# M868Hvrs2.net
KiCad netlist of a schematic drawn in EAGLE
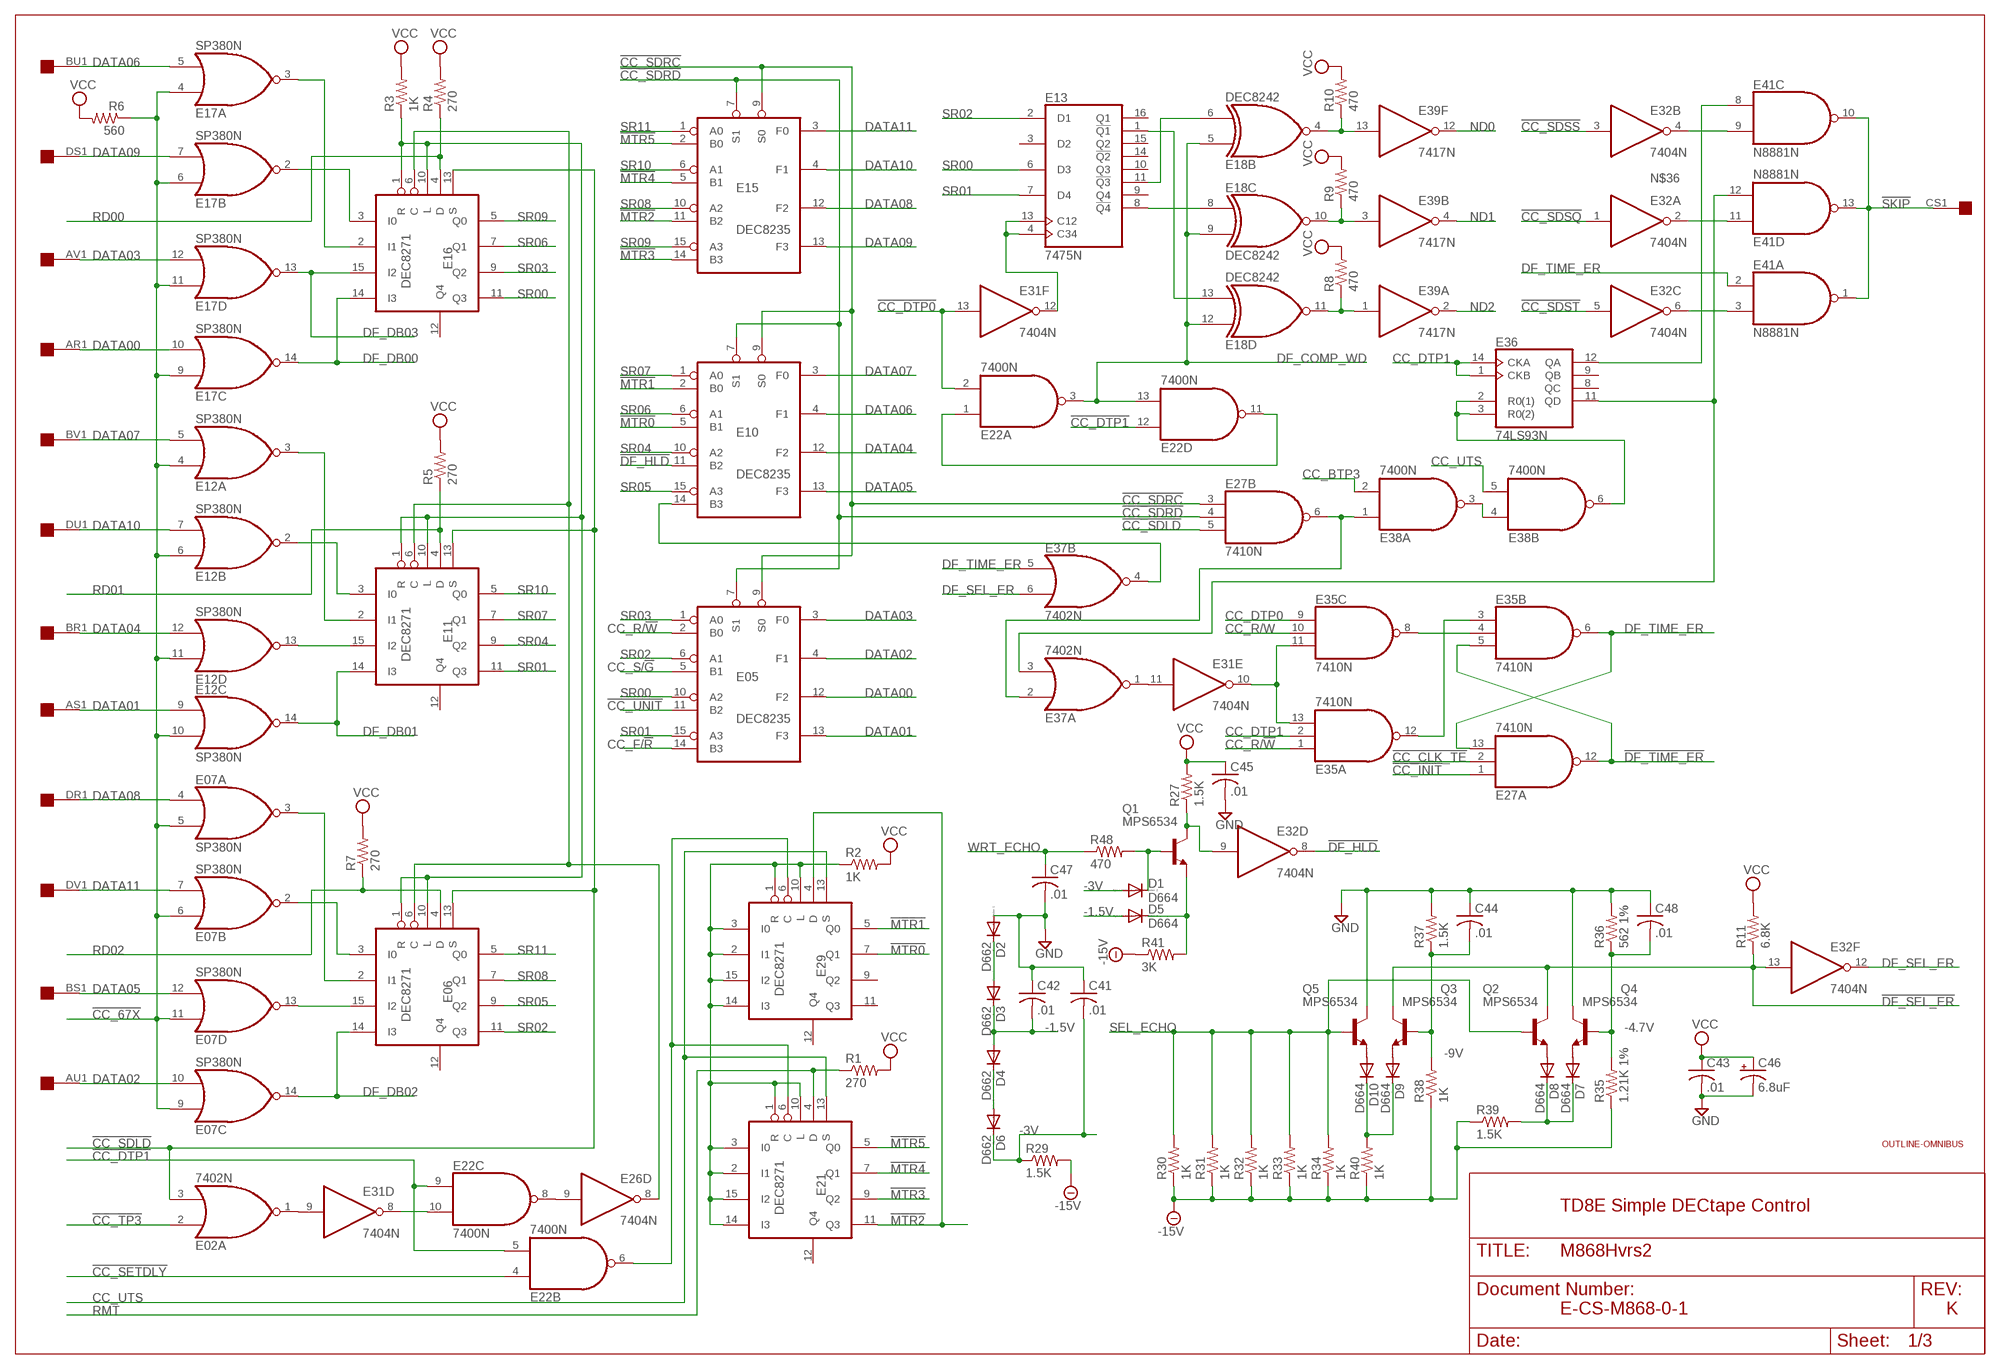
[diagram p0: schematic, sheet 1]
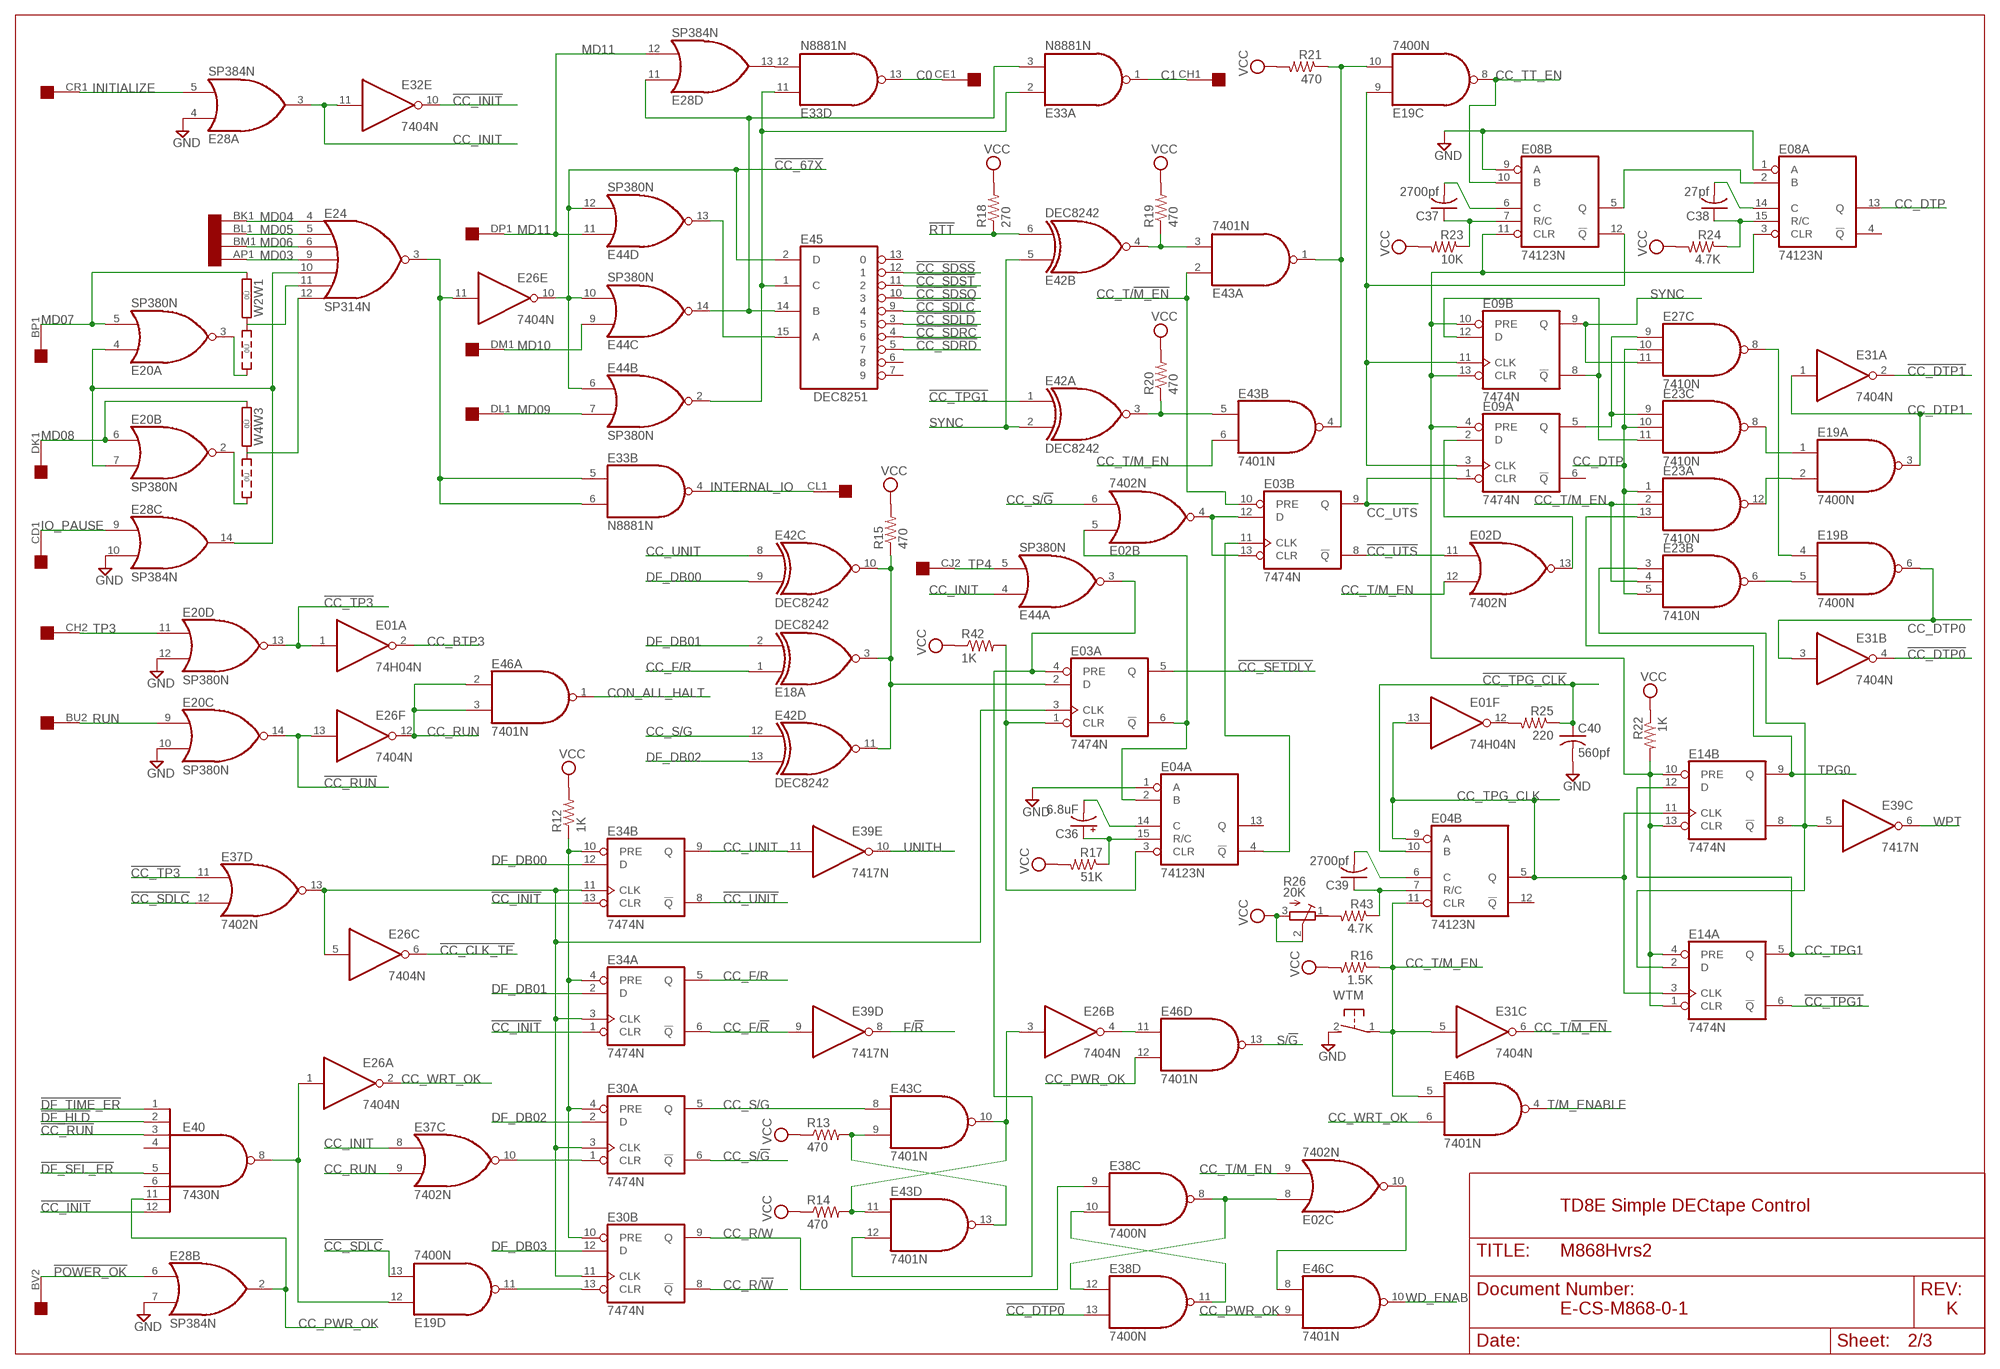
[diagram p1: schematic, sheet 2]
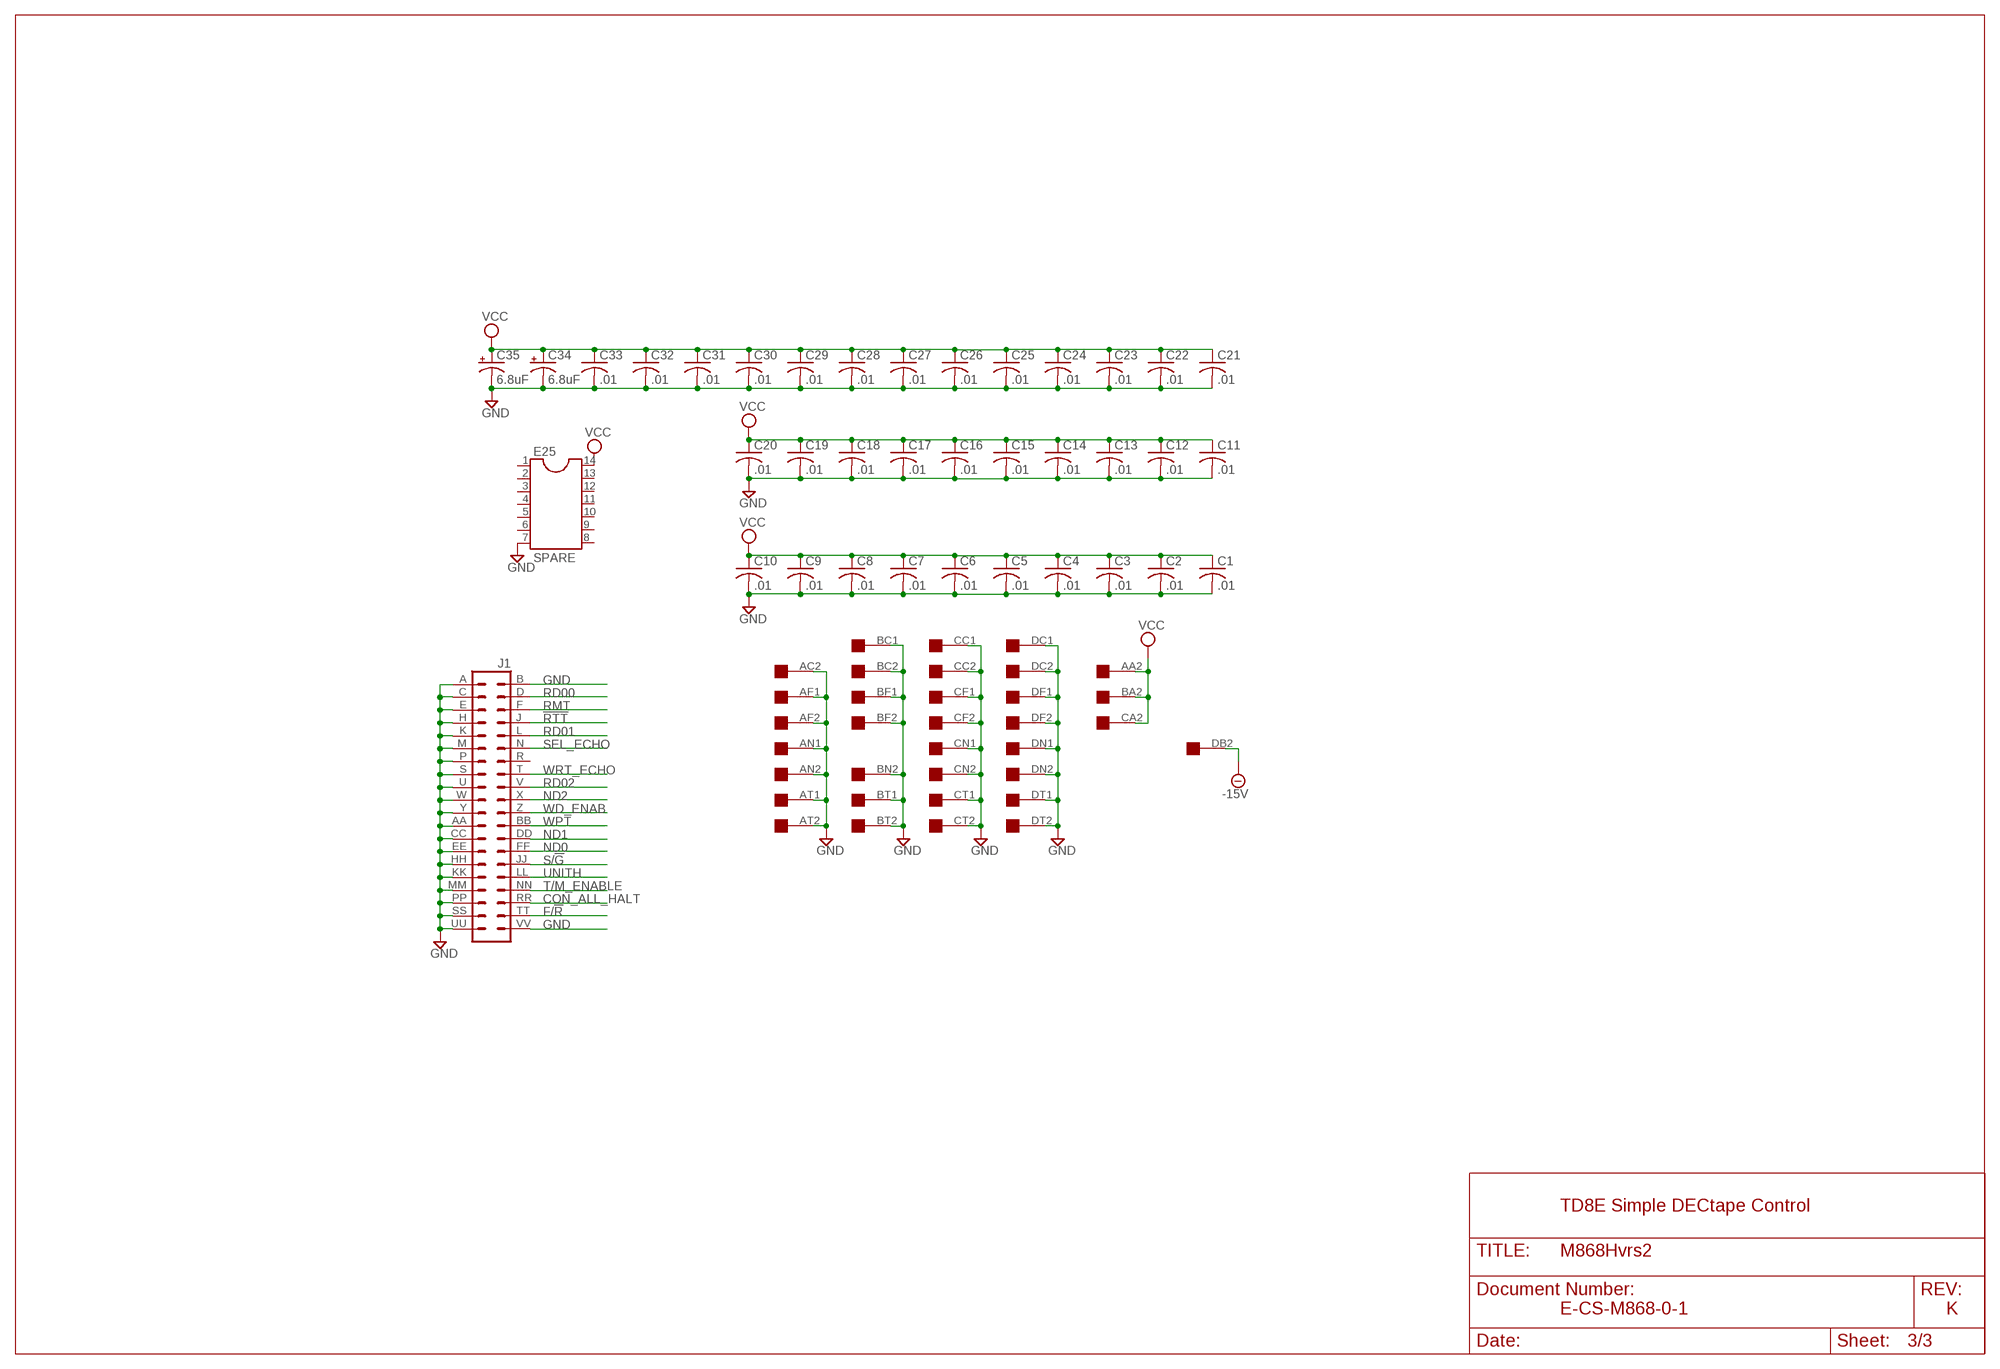
[diagram p2: schematic, sheet 3]

(export (version "E")
  (design (tool "Eeschema 10.0.6"))
  (components
    (comp (ref "C41")
      (value ".01")
      (footprint "eagle-import:C050-025X075")
      (libsource (lib "eagle-import") (part "C-US050-025X075"))
    )
    (comp (ref "C42")
      (value ".01")
      (footprint "eagle-import:C050-025X075")
      (libsource (lib "eagle-import") (part "C-US050-025X075"))
    )
    (comp (ref "C43")
      (value ".01")
      (footprint "eagle-import:C050-025X075")
      (libsource (lib "eagle-import") (part "C-US050-025X075"))
    )
    (comp (ref "C44")
      (value ".01")
      (footprint "eagle-import:C050-025X075")
      (libsource (lib "eagle-import") (part "C-US050-025X075"))
    )
    (comp (ref "C45")
      (value ".01")
      (footprint "eagle-import:C050-025X075")
      (libsource (lib "eagle-import") (part "C-US050-025X075"))
    )
    (comp (ref "C46")
      (value "6.8uF")
      (footprint "eagle-import:E12-8")
      (libsource (lib "eagle-import") (part "CPOL-USE20-8AXIAL"))
    )
    (comp (ref "C47")
      (value ".01")
      (footprint "eagle-import:C050-025X075")
      (libsource (lib "eagle-import") (part "C-US050-025X075"))
    )
    (comp (ref "C48")
      (value ".01")
      (footprint "eagle-import:C050-025X075")
      (libsource (lib "eagle-import") (part "C-US050-025X075"))
    )
    (comp (ref "D1")
      (value "D664")
      (footprint "eagle-import:DO35-10")
      (libsource (lib "eagle-import") (part "1N4148DO35-10"))
    )
    (comp (ref "D2")
      (value "D662")
      (footprint "eagle-import:DO35-10")
      (libsource (lib "eagle-import") (part "1N4148DO35-10"))
    )
    (comp (ref "D3")
      (value "D662")
      (footprint "eagle-import:DO35-10")
      (libsource (lib "eagle-import") (part "1N4148DO35-10"))
    )
    (comp (ref "D4")
      (value "D662")
      (footprint "eagle-import:DO35-10")
      (libsource (lib "eagle-import") (part "1N4148DO35-10"))
    )
    (comp (ref "D5")
      (value "D664")
      (footprint "eagle-import:DO35-10")
      (libsource (lib "eagle-import") (part "1N4148DO35-10"))
    )
    (comp (ref "D6")
      (value "D662")
      (footprint "eagle-import:DO35-10")
      (libsource (lib "eagle-import") (part "1N4148DO35-10"))
    )
    (comp (ref "D7")
      (value "D664")
      (footprint "eagle-import:DO35-10")
      (libsource (lib "eagle-import") (part "1N4148DO35-10"))
    )
    (comp (ref "D8")
      (value "D664")
      (footprint "eagle-import:DO35-10")
      (libsource (lib "eagle-import") (part "1N4148DO35-10"))
    )
    (comp (ref "D9")
      (value "D664")
      (footprint "eagle-import:DO35-10")
      (libsource (lib "eagle-import") (part "1N4148DO35-10"))
    )
    (comp (ref "D10")
      (value "D664")
      (footprint "eagle-import:DO35-10")
      (libsource (lib "eagle-import") (part "1N4148DO35-10"))
    )
    (comp (ref "E02")
      (value "7402N")
      (footprint "eagle-import:DIL14")
      (libsource (lib "eagle-import") (part "7402N"))
    )
    (comp (ref "E05")
      (value "DEC8235")
      (footprint "eagle-import:DIL16")
      (libsource (lib "eagle-import") (part "DEC8235"))
    )
    (comp (ref "E06")
      (value "DEC8271")
      (footprint "eagle-import:DIL16")
      (libsource (lib "eagle-import") (part "DEC8271"))
    )
    (comp (ref "E07")
      (value "SP380N")
      (footprint "eagle-import:DIL14")
      (libsource (lib "eagle-import") (part "SP380N"))
    )
    (comp (ref "E10")
      (value "DEC8235")
      (footprint "eagle-import:DIL16")
      (libsource (lib "eagle-import") (part "DEC8235"))
    )
    (comp (ref "E11")
      (value "DEC8271")
      (footprint "eagle-import:DIL16")
      (libsource (lib "eagle-import") (part "DEC8271"))
    )
    (comp (ref "E12")
      (value "SP380N")
      (footprint "eagle-import:DIL14")
      (libsource (lib "eagle-import") (part "SP380N"))
    )
    (comp (ref "E13")
      (value "7475N")
      (footprint "eagle-import:DIL16")
      (libsource (lib "eagle-import") (part "7475N"))
    )
    (comp (ref "E15")
      (value "DEC8235")
      (footprint "eagle-import:DIL16")
      (libsource (lib "eagle-import") (part "DEC8235"))
    )
    (comp (ref "E16")
      (value "DEC8271")
      (footprint "eagle-import:DIL16")
      (libsource (lib "eagle-import") (part "DEC8271"))
    )
    (comp (ref "E17")
      (value "SP380N")
      (footprint "eagle-import:DIL14")
      (libsource (lib "eagle-import") (part "SP380N"))
    )
    (comp (ref "E18")
      (value "DEC8242")
      (footprint "eagle-import:DIL14")
      (libsource (lib "eagle-import") (part "74266NLS"))
    )
    (comp (ref "E21")
      (value "DEC8271")
      (footprint "eagle-import:DIL16")
      (libsource (lib "eagle-import") (part "DEC8271"))
    )
    (comp (ref "E22")
      (value "7400N")
      (footprint "eagle-import:DIL14")
      (libsource (lib "eagle-import") (part "7400N"))
    )
    (comp (ref "E26")
      (value "7404N")
      (footprint "eagle-import:DIL14")
      (libsource (lib "eagle-import") (part "7404N"))
    )
    (comp (ref "E27")
      (value "7410N")
      (footprint "eagle-import:DIL14")
      (libsource (lib "eagle-import") (part "7410N"))
    )
    (comp (ref "E29")
      (value "DEC8271")
      (footprint "eagle-import:DIL16")
      (libsource (lib "eagle-import") (part "DEC8271"))
    )
    (comp (ref "E31")
      (value "7404N")
      (footprint "eagle-import:DIL14")
      (libsource (lib "eagle-import") (part "7404N"))
    )
    (comp (ref "E32")
      (value "7404N")
      (footprint "eagle-import:DIL14")
      (libsource (lib "eagle-import") (part "7404N"))
    )
    (comp (ref "E35")
      (value "7410N")
      (footprint "eagle-import:DIL14")
      (libsource (lib "eagle-import") (part "7410N"))
    )
    (comp (ref "E36")
      (value "74LS93N")
      (footprint "eagle-import:DIL14")
      (libsource (lib "eagle-import") (part "7493NLS"))
    )
    (comp (ref "E37")
      (value "7402N")
      (footprint "eagle-import:DIL14")
      (libsource (lib "eagle-import") (part "7402N"))
    )
    (comp (ref "E38")
      (value "7400N")
      (footprint "eagle-import:DIL14")
      (libsource (lib "eagle-import") (part "7400N"))
    )
    (comp (ref "E39")
      (value "7417N")
      (footprint "eagle-import:DIL14")
      (libsource (lib "eagle-import") (part "7417N"))
    )
    (comp (ref "E41")
      (value "N8881N")
      (footprint "eagle-import:DIL14")
      (libsource (lib "eagle-import") (part "N8881N"))
    )
    (comp (ref "EDGE$")
      (value "QUAD")
      (footprint "eagle-import:EDGE-CON8")
      (libsource (lib "eagle-import") (part "QUAD"))
    )
    (comp (ref "Q1")
      (value "MPS6534")
      (footprint "eagle-import:TO5")
      (libsource (lib "eagle-import") (part "2N2219"))
    )
    (comp (ref "Q2")
      (value "MPS6534")
      (footprint "eagle-import:TO5")
      (libsource (lib "eagle-import") (part "2N2219"))
    )
    (comp (ref "Q3")
      (value "MPS6534")
      (footprint "eagle-import:TO5")
      (libsource (lib "eagle-import") (part "2N2219"))
    )
    (comp (ref "Q4")
      (value "MPS6534")
      (footprint "eagle-import:TO5")
      (libsource (lib "eagle-import") (part "2N2219"))
    )
    (comp (ref "Q5")
      (value "MPS6534")
      (footprint "eagle-import:TO5")
      (libsource (lib "eagle-import") (part "2N2219"))
    )
    (comp (ref "R1")
      (value "270")
      (footprint "eagle-import:0207_10")
      (libsource (lib "eagle-import") (part "R-US_0207/10"))
    )
    (comp (ref "R2")
      (value "1K")
      (footprint "eagle-import:0207_10")
      (libsource (lib "eagle-import") (part "R-US_0207/10"))
    )
    (comp (ref "R3")
      (value "1K")
      (footprint "eagle-import:0207_10")
      (libsource (lib "eagle-import") (part "R-US_0207/10"))
    )
    (comp (ref "R4")
      (value "270")
      (footprint "eagle-import:0207_10")
      (libsource (lib "eagle-import") (part "R-US_0207/10"))
    )
    (comp (ref "R5")
      (value "270")
      (footprint "eagle-import:0207_10")
      (libsource (lib "eagle-import") (part "R-US_0207/10"))
    )
    (comp (ref "R6")
      (value "560")
      (footprint "eagle-import:0207_10")
      (libsource (lib "eagle-import") (part "R-US_0207/10"))
    )
    (comp (ref "R7")
      (value "270")
      (footprint "eagle-import:0207_10")
      (libsource (lib "eagle-import") (part "R-US_0207/10"))
    )
    (comp (ref "R8")
      (value "470")
      (footprint "eagle-import:0207_10")
      (libsource (lib "eagle-import") (part "R-US_0207/10"))
    )
    (comp (ref "R9")
      (value "470")
      (footprint "eagle-import:0207_10")
      (libsource (lib "eagle-import") (part "R-US_0207/10"))
    )
    (comp (ref "R10")
      (value "470")
      (footprint "eagle-import:0207_10")
      (libsource (lib "eagle-import") (part "R-US_0207/10"))
    )
    (comp (ref "R11")
      (value "6.8K")
      (footprint "eagle-import:0207_10")
      (libsource (lib "eagle-import") (part "R-US_0207/10"))
    )
    (comp (ref "R27")
      (value "1.5K")
      (footprint "eagle-import:0207_10")
      (libsource (lib "eagle-import") (part "R-US_0207/10"))
    )
    (comp (ref "R29")
      (value "1.5K")
      (footprint "eagle-import:0207_10")
      (libsource (lib "eagle-import") (part "R-US_0207/10"))
    )
    (comp (ref "R30")
      (value "1K")
      (footprint "eagle-import:0207_10")
      (libsource (lib "eagle-import") (part "R-US_0207/10"))
    )
    (comp (ref "R31")
      (value "1K")
      (footprint "eagle-import:0207_10")
      (libsource (lib "eagle-import") (part "R-US_0207/10"))
    )
    (comp (ref "R32")
      (value "1K")
      (footprint "eagle-import:0207_10")
      (libsource (lib "eagle-import") (part "R-US_0207/10"))
    )
    (comp (ref "R33")
      (value "1K")
      (footprint "eagle-import:0207_10")
      (libsource (lib "eagle-import") (part "R-US_0207/10"))
    )
    (comp (ref "R34")
      (value "1K")
      (footprint "eagle-import:0207_10")
      (libsource (lib "eagle-import") (part "R-US_0207/10"))
    )
    (comp (ref "R35")
      (value "1.21K 1%")
      (footprint "eagle-import:0207_15")
      (libsource (lib "eagle-import") (part "R-US_0207/15"))
    )
    (comp (ref "R36")
      (value "562 1%")
      (footprint "eagle-import:0207_15")
      (libsource (lib "eagle-import") (part "R-US_0207/15"))
    )
    (comp (ref "R37")
      (value "1.5K")
      (footprint "eagle-import:0207_10")
      (libsource (lib "eagle-import") (part "R-US_0207/10"))
    )
    (comp (ref "R38")
      (value "1K")
      (footprint "eagle-import:0207_10")
      (libsource (lib "eagle-import") (part "R-US_0207/10"))
    )
    (comp (ref "R39")
      (value "1.5K")
      (footprint "eagle-import:0207_10")
      (libsource (lib "eagle-import") (part "R-US_0207/10"))
    )
    (comp (ref "R40")
      (value "1K")
      (footprint "eagle-import:0207_10")
      (libsource (lib "eagle-import") (part "R-US_0207/10"))
    )
    (comp (ref "R41")
      (value "3K")
      (footprint "eagle-import:0207_10")
      (libsource (lib "eagle-import") (part "R-US_0207/10"))
    )
    (comp (ref "R48")
      (value "470")
      (footprint "eagle-import:0207_10")
      (libsource (lib "eagle-import") (part "R-US_0207/10"))
    )
    (comp (ref "U$1")
      (value "OUTLINE-OMNIBUS")
      (footprint "eagle-import:OMNIBUS")
      (libsource (lib "eagle-import") (part "OUTLINE-OMNIBUS"))
    )
    (comp (ref "C36")
      (value "6.8uF")
      (footprint "eagle-import:E12-8")
      (libsource (lib "eagle-import") (part "CPOL-USE20-8AXIAL"))
    )
    (comp (ref "C37")
      (value "2700pf")
      (footprint "eagle-import:C102-043X133")
      (libsource (lib "eagle-import") (part "C-US102-043X133"))
    )
    (comp (ref "C38")
      (value "27pf")
      (footprint "eagle-import:C050-025X075")
      (libsource (lib "eagle-import") (part "C-US050-025X075"))
    )
    (comp (ref "C39")
      (value "2700pf")
      (footprint "eagle-import:C102-043X133")
      (libsource (lib "eagle-import") (part "C-US102-043X133"))
    )
    (comp (ref "C40")
      (value "560pf")
      (footprint "eagle-import:C075-032X103")
      (libsource (lib "eagle-import") (part "C-US075-032X103"))
    )
    (comp (ref "E01")
      (value "74H04N")
      (footprint "eagle-import:DIL14")
      (libsource (lib "eagle-import") (part "7404NS"))
    )
    (comp (ref "E03")
      (value "7474N")
      (footprint "eagle-import:DIL14")
      (libsource (lib "eagle-import") (part "7474NS"))
    )
    (comp (ref "E04")
      (value "74123N")
      (footprint "eagle-import:DIL16")
      (libsource (lib "eagle-import") (part "74123N"))
    )
    (comp (ref "E08")
      (value "74123N")
      (footprint "eagle-import:DIL16")
      (libsource (lib "eagle-import") (part "74123N"))
    )
    (comp (ref "E09")
      (value "7474N")
      (footprint "eagle-import:DIL14")
      (libsource (lib "eagle-import") (part "7474NS"))
    )
    (comp (ref "E14")
      (value "7474N")
      (footprint "eagle-import:DIL14")
      (libsource (lib "eagle-import") (part "7474NS"))
    )
    (comp (ref "E19")
      (value "7400N")
      (footprint "eagle-import:DIL14")
      (libsource (lib "eagle-import") (part "7400N"))
    )
    (comp (ref "E20")
      (value "SP380N")
      (footprint "eagle-import:DIL14")
      (libsource (lib "eagle-import") (part "SP380N"))
    )
    (comp (ref "E23")
      (value "7410N")
      (footprint "eagle-import:DIL14")
      (libsource (lib "eagle-import") (part "7410N"))
    )
    (comp (ref "E24")
      (value "SP314N")
      (footprint "eagle-import:DIL14")
      (libsource (lib "eagle-import") (part "SP314N"))
    )
    (comp (ref "E28")
      (value "SP384N")
      (footprint "eagle-import:DIL14")
      (libsource (lib "eagle-import") (part "SP384N"))
    )
    (comp (ref "E30")
      (value "7474N")
      (footprint "eagle-import:DIL14")
      (libsource (lib "eagle-import") (part "7474NS"))
    )
    (comp (ref "E33")
      (value "N8881N")
      (footprint "eagle-import:DIL14")
      (libsource (lib "eagle-import") (part "N8881N"))
    )
    (comp (ref "E34")
      (value "7474N")
      (footprint "eagle-import:DIL14")
      (libsource (lib "eagle-import") (part "7474NS"))
    )
    (comp (ref "E40")
      (value "7430N")
      (footprint "eagle-import:DIL14")
      (libsource (lib "eagle-import") (part "7430N"))
    )
    (comp (ref "E42")
      (value "DEC8242")
      (footprint "eagle-import:DIL14")
      (libsource (lib "eagle-import") (part "74266NLS"))
    )
    (comp (ref "E43")
      (value "7401N")
      (footprint "eagle-import:DIL14")
      (libsource (lib "eagle-import") (part "7401NLS"))
    )
    (comp (ref "E44")
      (value "SP380N")
      (footprint "eagle-import:DIL14")
      (libsource (lib "eagle-import") (part "SP380N"))
    )
    (comp (ref "E45")
      (value "DEC8251")
      (footprint "eagle-import:DIL16")
      (libsource (lib "eagle-import") (part "DEC8251"))
    )
    (comp (ref "E46")
      (value "7401N")
      (footprint "eagle-import:DIL14")
      (libsource (lib "eagle-import") (part "7401NLS"))
    )
    (comp (ref "R12")
      (value "1K")
      (footprint "eagle-import:0207_10")
      (libsource (lib "eagle-import") (part "R-US_0207/10"))
    )
    (comp (ref "R13")
      (value "470")
      (footprint "eagle-import:0207_10")
      (libsource (lib "eagle-import") (part "R-US_0207/10"))
    )
    (comp (ref "R14")
      (value "470")
      (footprint "eagle-import:0207_10")
      (libsource (lib "eagle-import") (part "R-US_0207/10"))
    )
    (comp (ref "R15")
      (value "470")
      (footprint "eagle-import:0207_10")
      (libsource (lib "eagle-import") (part "R-US_0207/10"))
    )
    (comp (ref "R16")
      (value "1.5K")
      (footprint "eagle-import:0207_10")
      (libsource (lib "eagle-import") (part "R-US_0207/10"))
    )
    (comp (ref "R17")
      (value "51K")
      (footprint "eagle-import:0207_10")
      (libsource (lib "eagle-import") (part "R-US_0207/10"))
    )
    (comp (ref "R18")
      (value "270")
      (footprint "eagle-import:0207_10")
      (libsource (lib "eagle-import") (part "R-US_0207/10"))
    )
    (comp (ref "R19")
      (value "470")
      (footprint "eagle-import:0207_10")
      (libsource (lib "eagle-import") (part "R-US_0207/10"))
    )
    (comp (ref "R20")
      (value "470")
      (footprint "eagle-import:0207_10")
      (libsource (lib "eagle-import") (part "R-US_0207/10"))
    )
    (comp (ref "R21")
      (value "470")
      (footprint "eagle-import:0207_10")
      (libsource (lib "eagle-import") (part "R-US_0207/10"))
    )
    (comp (ref "R22")
      (value "1K")
      (footprint "eagle-import:0207_10")
      (libsource (lib "eagle-import") (part "R-US_0207/10"))
    )
    (comp (ref "R23")
      (value "10K")
      (footprint "eagle-import:0207_10")
      (libsource (lib "eagle-import") (part "R-US_0207/10"))
    )
    (comp (ref "R24")
      (value "4.7K")
      (footprint "eagle-import:0207_10")
      (libsource (lib "eagle-import") (part "R-US_0207/10"))
    )
    (comp (ref "R25")
      (value "220")
      (footprint "eagle-import:0207_10")
      (libsource (lib "eagle-import") (part "R-US_0207/10"))
    )
    (comp (ref "R26")
      (value "20K")
      (footprint "eagle-import:3006Y")
      (libsource (lib "eagle-import") (part "275P"))
    )
    (comp (ref "R42")
      (value "1K")
      (footprint "eagle-import:0207_10")
      (libsource (lib "eagle-import") (part "R-US_0207/10"))
    )
    (comp (ref "R43")
      (value "4.7K")
      (footprint "eagle-import:0207_10")
      (libsource (lib "eagle-import") (part "R-US_0207/10"))
    )
    (comp (ref "W2W1")
      (value "0R2")
      (footprint "eagle-import:0R2_10")
      (libsource (lib "eagle-import") (part "0R2"))
    )
    (comp (ref "W4W3")
      (value "0R2")
      (footprint "eagle-import:0R2_10")
      (libsource (lib "eagle-import") (part "0R2"))
    )
    (comp (ref "WTM")
      (value "31-XX")
      (footprint "eagle-import:B3F-31XX")
      (fields (field (name "MPN") "B3F-3100"))
      (libsource (lib "eagle-import") (part "31-XX"))
    )
    (comp (ref "C1")
      (value ".01")
      (footprint "eagle-import:C050-025X075")
      (libsource (lib "eagle-import") (part "C-US050-025X075"))
    )
    (comp (ref "C2")
      (value ".01")
      (footprint "eagle-import:C050-025X075")
      (libsource (lib "eagle-import") (part "C-US050-025X075"))
    )
    (comp (ref "C3")
      (value ".01")
      (footprint "eagle-import:C050-025X075")
      (libsource (lib "eagle-import") (part "C-US050-025X075"))
    )
    (comp (ref "C4")
      (value ".01")
      (footprint "eagle-import:C050-025X075")
      (libsource (lib "eagle-import") (part "C-US050-025X075"))
    )
    (comp (ref "C5")
      (value ".01")
      (footprint "eagle-import:C050-025X075")
      (libsource (lib "eagle-import") (part "C-US050-025X075"))
    )
    (comp (ref "C6")
      (value ".01")
      (footprint "eagle-import:C050-025X075")
      (libsource (lib "eagle-import") (part "C-US050-025X075"))
    )
    (comp (ref "C7")
      (value ".01")
      (footprint "eagle-import:C050-025X075")
      (libsource (lib "eagle-import") (part "C-US050-025X075"))
    )
    (comp (ref "C8")
      (value ".01")
      (footprint "eagle-import:C050-025X075")
      (libsource (lib "eagle-import") (part "C-US050-025X075"))
    )
    (comp (ref "C9")
      (value ".01")
      (footprint "eagle-import:C050-025X075")
      (libsource (lib "eagle-import") (part "C-US050-025X075"))
    )
    (comp (ref "C10")
      (value ".01")
      (footprint "eagle-import:C050-025X075")
      (libsource (lib "eagle-import") (part "C-US050-025X075"))
    )
    (comp (ref "C11")
      (value ".01")
      (footprint "eagle-import:C050-025X075")
      (libsource (lib "eagle-import") (part "C-US050-025X075"))
    )
    (comp (ref "C12")
      (value ".01")
      (footprint "eagle-import:C050-025X075")
      (libsource (lib "eagle-import") (part "C-US050-025X075"))
    )
    (comp (ref "C13")
      (value ".01")
      (footprint "eagle-import:C050-025X075")
      (libsource (lib "eagle-import") (part "C-US050-025X075"))
    )
    (comp (ref "C14")
      (value ".01")
      (footprint "eagle-import:C050-025X075")
      (libsource (lib "eagle-import") (part "C-US050-025X075"))
    )
    (comp (ref "C15")
      (value ".01")
      (footprint "eagle-import:C050-025X075")
      (libsource (lib "eagle-import") (part "C-US050-025X075"))
    )
    (comp (ref "C16")
      (value ".01")
      (footprint "eagle-import:C050-025X075")
      (libsource (lib "eagle-import") (part "C-US050-025X075"))
    )
    (comp (ref "C17")
      (value ".01")
      (footprint "eagle-import:C050-025X075")
      (libsource (lib "eagle-import") (part "C-US050-025X075"))
    )
    (comp (ref "C18")
      (value ".01")
      (footprint "eagle-import:C050-025X075")
      (libsource (lib "eagle-import") (part "C-US050-025X075"))
    )
    (comp (ref "C19")
      (value ".01")
      (footprint "eagle-import:C050-025X075")
      (libsource (lib "eagle-import") (part "C-US050-025X075"))
    )
    (comp (ref "C20")
      (value ".01")
      (footprint "eagle-import:C050-025X075")
      (libsource (lib "eagle-import") (part "C-US050-025X075"))
    )
    (comp (ref "C21")
      (value ".01")
      (footprint "eagle-import:C050-025X075")
      (libsource (lib "eagle-import") (part "C-US050-025X075"))
    )
    (comp (ref "C22")
      (value ".01")
      (footprint "eagle-import:C050-025X075")
      (libsource (lib "eagle-import") (part "C-US050-025X075"))
    )
    (comp (ref "C23")
      (value ".01")
      (footprint "eagle-import:C050-025X075")
      (libsource (lib "eagle-import") (part "C-US050-025X075"))
    )
    (comp (ref "C24")
      (value ".01")
      (footprint "eagle-import:C050-025X075")
      (libsource (lib "eagle-import") (part "C-US050-025X075"))
    )
    (comp (ref "C25")
      (value ".01")
      (footprint "eagle-import:C050-025X075")
      (libsource (lib "eagle-import") (part "C-US050-025X075"))
    )
    (comp (ref "C26")
      (value ".01")
      (footprint "eagle-import:C050-025X075")
      (libsource (lib "eagle-import") (part "C-US050-025X075"))
    )
    (comp (ref "C27")
      (value ".01")
      (footprint "eagle-import:C050-025X075")
      (libsource (lib "eagle-import") (part "C-US050-025X075"))
    )
    (comp (ref "C28")
      (value ".01")
      (footprint "eagle-import:C050-025X075")
      (libsource (lib "eagle-import") (part "C-US050-025X075"))
    )
    (comp (ref "C29")
      (value ".01")
      (footprint "eagle-import:C050-025X075")
      (libsource (lib "eagle-import") (part "C-US050-025X075"))
    )
    (comp (ref "C30")
      (value ".01")
      (footprint "eagle-import:C050-025X075")
      (libsource (lib "eagle-import") (part "C-US050-025X075"))
    )
    (comp (ref "C31")
      (value ".01")
      (footprint "eagle-import:C050-025X075")
      (libsource (lib "eagle-import") (part "C-US050-025X075"))
    )
    (comp (ref "C32")
      (value ".01")
      (footprint "eagle-import:C050-025X075")
      (libsource (lib "eagle-import") (part "C-US050-025X075"))
    )
    (comp (ref "C33")
      (value ".01")
      (footprint "eagle-import:C050-025X075")
      (libsource (lib "eagle-import") (part "C-US050-025X075"))
    )
    (comp (ref "C34")
      (value "6.8uF")
      (footprint "eagle-import:E12-8")
      (libsource (lib "eagle-import") (part "CPOL-USE20-8AXIAL"))
    )
    (comp (ref "C35")
      (value "6.8uF")
      (footprint "eagle-import:E12-8")
      (libsource (lib "eagle-import") (part "CPOL-USE20-8AXIAL"))
    )
    (comp (ref "E25")
      (value "SPARE")
      (footprint "eagle-import:DIL14")
      (libsource (lib "eagle-import") (part "DIL14"))
    )
    (comp (ref "J1")
      (value "DEC40PINH")
      (footprint "eagle-import:DEC40PINH")
      (libsource (lib "eagle-import") (part "DEC40PINH"))
    )
  )
  (nets
    (net (code "1") (name "-1.5V") (class "Default")
      (node (ref "C42") (pin "2") (pinfunction "2_2") (pintype "passive"))
      (node (ref "D3") (pin "C") (pinfunction "C_C") (pintype "passive"))
      (node (ref "D4") (pin "A") (pinfunction "A_A") (pintype "passive"))
      (node (ref "D5") (pin "A") (pinfunction "A_A") (pintype "passive"))
    )
    (net (code "2") (name "-3V") (class "Default")
      (node (ref "C41") (pin "2") (pinfunction "2_2") (pintype "passive"))
      (node (ref "D1") (pin "A") (pinfunction "A_A") (pintype "passive"))
      (node (ref "D6") (pin "C") (pinfunction "C_C") (pintype "passive"))
      (node (ref "R29") (pin "1") (pinfunction "1_1") (pintype "passive"))
    )
    (net (code "3") (name "-4.7V") (class "Default")
      (node (ref "C48") (pin "2") (pinfunction "2_2") (pintype "passive"))
      (node (ref "Q4") (pin "2") (pinfunction "B_2") (pintype "passive"))
      (node (ref "R35") (pin "2") (pinfunction "2_2") (pintype "passive"))
      (node (ref "R36") (pin "1") (pinfunction "1_1") (pintype "passive"))
    )
    (net (code "4") (name "-9V") (class "Default")
      (node (ref "C44") (pin "2") (pinfunction "2_2") (pintype "passive"))
      (node (ref "Q3") (pin "2") (pinfunction "B_2") (pintype "passive"))
      (node (ref "R37") (pin "1") (pinfunction "1_1") (pintype "passive"))
      (node (ref "R38") (pin "2") (pinfunction "2_2") (pintype "passive"))
    )
    (net (code "5") (name "-15V") (class "Default")
      (node (ref "EDGE$") (pin "DB2") (pinfunction "1_DB2") (pintype "bidirectional"))
      (node (ref "R29") (pin "2") (pinfunction "2_2") (pintype "passive"))
      (node (ref "R30") (pin "1") (pinfunction "1_1") (pintype "passive"))
      (node (ref "R31") (pin "1") (pinfunction "1_1") (pintype "passive"))
      (node (ref "R32") (pin "1") (pinfunction "1_1") (pintype "passive"))
      (node (ref "R33") (pin "1") (pinfunction "1_1") (pintype "passive"))
      (node (ref "R34") (pin "1") (pinfunction "1_1") (pintype "passive"))
      (node (ref "R35") (pin "1") (pinfunction "1_1") (pintype "passive"))
      (node (ref "R38") (pin "1") (pinfunction "1_1") (pintype "passive"))
      (node (ref "R39") (pin "1") (pinfunction "1_1") (pintype "passive"))
      (node (ref "R40") (pin "1") (pinfunction "1_1") (pintype "passive"))
      (node (ref "R41") (pin "1") (pinfunction "1_1") (pintype "passive"))
    )
    (net (code "6") (name "C0") (class "Default")
      (node (ref "E33") (pin "13") (pinfunction "O_13") (pintype "open_collector"))
      (node (ref "EDGE$") (pin "CE1") (pinfunction "1_CE1") (pintype "bidirectional"))
    )
    (net (code "7") (name "C1") (class "Default")
      (node (ref "E33") (pin "1") (pinfunction "O_1") (pintype "open_collector"))
      (node (ref "EDGE$") (pin "CH1") (pinfunction "1_CH1") (pintype "bidirectional"))
    )
    (net (code "8") (name "CC_BTP3") (class "Default")
      (node (ref "E01") (pin "2") (pinfunction "O_2") (pintype "output"))
      (node (ref "E38") (pin "2") (pinfunction "I1_2") (pintype "input"))
    )
    (net (code "9") (name "CC_DTP") (class "Default")
      (node (ref "E08") (pin "13") (pinfunction "Q_13") (pintype "output"))
      (node (ref "E23") (pin "1") (pinfunction "I0_1") (pintype "input"))
      (node (ref "E23") (pin "10") (pinfunction "I1_10") (pintype "input"))
      (node (ref "E23") (pin "5") (pinfunction "I2_5") (pintype "input"))
      (node (ref "E27") (pin "10") (pinfunction "I1_10") (pintype "input"))
    )
    (net (code "10") (name "CC_DTP0") (class "Default")
      (node (ref "E19") (pin "6") (pinfunction "O_6") (pintype "output"))
      (node (ref "E31") (pin "3") (pinfunction "I_3") (pintype "input"))
      (node (ref "E35") (pin "9") (pinfunction "I0_9") (pintype "input"))
    )
    (net (code "11") (name "CC_DTP1") (class "Default")
      (node (ref "E19") (pin "3") (pinfunction "O_3") (pintype "output"))
      (node (ref "E31") (pin "1") (pinfunction "I_1") (pintype "input"))
      (node (ref "E35") (pin "2") (pinfunction "I1_2") (pintype "input"))
      (node (ref "E36") (pin "1") (pinfunction "CKB_1") (pintype "input"))
      (node (ref "E36") (pin "14") (pinfunction "CKA_14") (pintype "input"))
    )
    (net (code "12") (name "CC_F{slash}R") (class "Default")
      (node (ref "E18") (pin "1") (pinfunction "I0_1") (pintype "input"))
      (node (ref "E34") (pin "5") (pinfunction "Q_5") (pintype "output"))
    )
    (net (code "13") (name "CC_F{slash}~{R}") (class "Default")
      (node (ref "E05") (pin "14") (pinfunction "B3_14") (pintype "input"))
      (node (ref "E34") (pin "6") (pinfunction "~{Q}_6") (pintype "output"))
      (node (ref "E39") (pin "9") (pinfunction "I_9") (pintype "input"))
    )
    (net (code "14") (name "CC_INIT") (class "Default")
      (node (ref "E28") (pin "3") (pinfunction "O_3") (pintype "output"))
      (node (ref "E32") (pin "11") (pinfunction "I_11") (pintype "input"))
      (node (ref "E37") (pin "8") (pinfunction "I0_8") (pintype "input"))
      (node (ref "E44") (pin "4") (pinfunction "I0_4") (pintype "input"))
    )
    (net (code "15") (name "CC_PWR_OK") (class "Default")
      (node (ref "E28") (pin "2") (pinfunction "O_2") (pintype "output"))
      (node (ref "E40") (pin "11") (pinfunction "I6_11") (pintype "input"))
      (node (ref "E46") (pin "12") (pinfunction "I1_12") (pintype "input"))
      (node (ref "E46") (pin "9") (pinfunction "I1_9") (pintype "input"))
    )
    (net (code "16") (name "CC_RUN") (class "Default")
      (node (ref "E26") (pin "12") (pinfunction "O_12") (pintype "output"))
      (node (ref "E37") (pin "9") (pinfunction "I1_9") (pintype "input"))
      (node (ref "E46") (pin "2") (pinfunction "I0_2") (pintype "input"))
      (node (ref "E46") (pin "3") (pinfunction "I1_3") (pintype "input"))
    )
    (net (code "17") (name "CC_R{slash}W") (class "Default")
      (node (ref "E30") (pin "9") (pinfunction "Q_9") (pintype "output"))
      (node (ref "E35") (pin "10") (pinfunction "I1_10") (pintype "input"))
      (node (ref "E38") (pin "9") (pinfunction "I0_9") (pintype "input"))
    )
    (net (code "18") (name "CC_R{slash}~{W}") (class "Default")
      (node (ref "E05") (pin "2") (pinfunction "B0_2") (pintype "input"))
      (node (ref "E30") (pin "8") (pinfunction "~{Q}_8") (pintype "output"))
      (node (ref "E35") (pin "1") (pinfunction "I0_1") (pintype "input"))
    )
    (net (code "19") (name "CC_S{slash}G") (class "Default")
      (node (ref "E30") (pin "5") (pinfunction "Q_5") (pintype "output"))
      (node (ref "E42") (pin "12") (pinfunction "I0_12") (pintype "input"))
      (node (ref "E43") (pin "8") (pinfunction "I0_8") (pintype "input"))
    )
    (net (code "20") (name "CC_S{slash}~{G}") (class "Default")
      (node (ref "E02") (pin "6") (pinfunction "I1_6") (pintype "input"))
      (node (ref "E05") (pin "5") (pinfunction "B1_5") (pintype "input"))
      (node (ref "E30") (pin "6") (pinfunction "~{Q}_6") (pintype "output"))
    )
    (net (code "21") (name "CC_TPG1") (class "Default")
      (node (ref "E14") (pin "12") (pinfunction "D_12") (pintype "input"))
      (node (ref "E14") (pin "5") (pinfunction "Q_5") (pintype "output"))
    )
    (net (code "22") (name "CC_TPG_CLK") (class "Default")
      (node (ref "E01") (pin "13") (pinfunction "I_13") (pintype "input"))
      (node (ref "E04") (pin "5") (pinfunction "Q_5") (pintype "output"))
      (node (ref "E04") (pin "9") (pinfunction "A_9") (pintype "input"))
      (node (ref "E14") (pin "11") (pinfunction "CLK_11") (pintype "input"))
      (node (ref "E14") (pin "3") (pinfunction "CLK_3") (pintype "input"))
    )
    (net (code "23") (name "CC_TT_EN") (class "Default")
      (node (ref "E08") (pin "10") (pinfunction "B_10") (pintype "input"))
      (node (ref "E19") (pin "8") (pinfunction "O_8") (pintype "output"))
    )
    (net (code "24") (name "CC_T{slash}M_EN") (class "Default")
      (node (ref "E02") (pin "12") (pinfunction "I1_12") (pintype "input"))
      (node (ref "E02") (pin "9") (pinfunction "I1_9") (pintype "input"))
      (node (ref "E04") (pin "11") (pinfunction "CLR_11") (pintype "input"))
      (node (ref "E23") (pin "2") (pinfunction "I1_2") (pintype "input"))
      (node (ref "E23") (pin "4") (pinfunction "I1_4") (pintype "input"))
      (node (ref "E31") (pin "5") (pinfunction "I_5") (pintype "input"))
      (node (ref "E43") (pin "6") (pinfunction "I1_6") (pintype "input"))
      (node (ref "E46") (pin "5") (pinfunction "I0_5") (pintype "input"))
      (node (ref "R16") (pin "1") (pinfunction "1_1") (pintype "passive"))
      (node (ref "WTM") (pin "1") (pinfunction "P_1") (pintype "passive"))
    )
    (net (code "25") (name "CC_T{slash}~{M_EN}") (class "Default")
      (node (ref "E03") (pin "10") (pinfunction "PRE_10") (pintype "input"))
      (node (ref "E31") (pin "6") (pinfunction "O_6") (pintype "output"))
      (node (ref "E43") (pin "2") (pinfunction "I0_2") (pintype "input"))
    )
    (net (code "26") (name "CC_UNIT") (class "Default")
      (node (ref "E34") (pin "9") (pinfunction "Q_9") (pintype "output"))
      (node (ref "E39") (pin "11") (pinfunction "I_11") (pintype "input"))
      (node (ref "E42") (pin "8") (pinfunction "I0_8") (pintype "input"))
    )
    (net (code "27") (name "CC_UTS") (class "Default")
      (node (ref "E03") (pin "9") (pinfunction "Q_9") (pintype "output"))
      (node (ref "E09") (pin "1") (pinfunction "CLR_1") (pintype "input"))
      (node (ref "E21") (pin "13") (pinfunction "S_13") (pintype "input"))
      (node (ref "E29") (pin "13") (pinfunction "S_13") (pintype "input"))
      (node (ref "E38") (pin "5") (pinfunction "I1_5") (pintype "input"))
    )
    (net (code "28") (name "CC_WRT_OK") (class "Default")
      (node (ref "E26") (pin "2") (pinfunction "O_2") (pintype "output"))
      (node (ref "E46") (pin "6") (pinfunction "I1_6") (pintype "input"))
    )
    (net (code "29") (name "CON_ALL_HALT") (class "Default")
      (node (ref "E46") (pin "1") (pinfunction "O_1") (pintype "open_collector"))
      (node (ref "J1") (pin "RR") (pinfunction "36_RR") (pintype "bidirectional"))
    )
    (net (code "30") (name "DATA00") (class "Default")
      (node (ref "E05") (pin "12") (pinfunction "F2_12") (pintype "open_collector"))
      (node (ref "E17") (pin "10") (pinfunction "I1_10") (pintype "input"))
      (node (ref "EDGE$") (pin "AR1") (pinfunction "1_AR1") (pintype "bidirectional"))
    )
    (net (code "31") (name "DATA01") (class "Default")
      (node (ref "E05") (pin "13") (pinfunction "F3_13") (pintype "open_collector"))
      (node (ref "E12") (pin "9") (pinfunction "I0_9") (pintype "input"))
      (node (ref "EDGE$") (pin "AS1") (pinfunction "1_AS1") (pintype "bidirectional"))
    )
    (net (code "32") (name "DATA02") (class "Default")
      (node (ref "E05") (pin "4") (pinfunction "F1_4") (pintype "open_collector"))
      (node (ref "E07") (pin "10") (pinfunction "I1_10") (pintype "input"))
      (node (ref "EDGE$") (pin "AU1") (pinfunction "1_AU1") (pintype "bidirectional"))
    )
    (net (code "33") (name "DATA03") (class "Default")
      (node (ref "E05") (pin "3") (pinfunction "F0_3") (pintype "open_collector"))
      (node (ref "E17") (pin "12") (pinfunction "I1_12") (pintype "input"))
      (node (ref "EDGE$") (pin "AV1") (pinfunction "1_AV1") (pintype "bidirectional"))
    )
    (net (code "34") (name "DATA04") (class "Default")
      (node (ref "E10") (pin "12") (pinfunction "F2_12") (pintype "open_collector"))
      (node (ref "E12") (pin "12") (pinfunction "I1_12") (pintype "input"))
      (node (ref "EDGE$") (pin "BR1") (pinfunction "1_BR1") (pintype "bidirectional"))
    )
    (net (code "35") (name "DATA05") (class "Default")
      (node (ref "E07") (pin "12") (pinfunction "I1_12") (pintype "input"))
      (node (ref "E10") (pin "13") (pinfunction "F3_13") (pintype "open_collector"))
      (node (ref "EDGE$") (pin "BS1") (pinfunction "1_BS1") (pintype "bidirectional"))
    )
    (net (code "36") (name "DATA06") (class "Default")
      (node (ref "E10") (pin "4") (pinfunction "F1_4") (pintype "open_collector"))
      (node (ref "E17") (pin "5") (pinfunction "I1_5") (pintype "input"))
      (node (ref "EDGE$") (pin "BU1") (pinfunction "1_BU1") (pintype "bidirectional"))
    )
    (net (code "37") (name "DATA07") (class "Default")
      (node (ref "E10") (pin "3") (pinfunction "F0_3") (pintype "open_collector"))
      (node (ref "E12") (pin "5") (pinfunction "I1_5") (pintype "input"))
      (node (ref "EDGE$") (pin "BV1") (pinfunction "1_BV1") (pintype "bidirectional"))
    )
    (net (code "38") (name "DATA08") (class "Default")
      (node (ref "E07") (pin "4") (pinfunction "I0_4") (pintype "input"))
      (node (ref "E15") (pin "12") (pinfunction "F2_12") (pintype "open_collector"))
      (node (ref "EDGE$") (pin "DR1") (pinfunction "1_DR1") (pintype "bidirectional"))
    )
    (net (code "39") (name "DATA09") (class "Default")
      (node (ref "E15") (pin "13") (pinfunction "F3_13") (pintype "open_collector"))
      (node (ref "E17") (pin "7") (pinfunction "I1_7") (pintype "input"))
      (node (ref "EDGE$") (pin "DS1") (pinfunction "1_DS1") (pintype "bidirectional"))
    )
    (net (code "40") (name "DATA10") (class "Default")
      (node (ref "E12") (pin "7") (pinfunction "I1_7") (pintype "input"))
      (node (ref "E15") (pin "4") (pinfunction "F1_4") (pintype "open_collector"))
      (node (ref "EDGE$") (pin "DU1") (pinfunction "1_DU1") (pintype "bidirectional"))
    )
    (net (code "41") (name "DATA11") (class "Default")
      (node (ref "E07") (pin "7") (pinfunction "I1_7") (pintype "input"))
      (node (ref "E15") (pin "3") (pinfunction "F0_3") (pintype "open_collector"))
      (node (ref "EDGE$") (pin "DV1") (pinfunction "1_DV1") (pintype "bidirectional"))
    )
    (net (code "42") (name "DF_COMP_WD") (class "Default")
      (node (ref "E18") (pin "12") (pinfunction "I0_12") (pintype "input"))
      (node (ref "E18") (pin "5") (pinfunction "I0_5") (pintype "input"))
      (node (ref "E18") (pin "9") (pinfunction "I1_9") (pintype "input"))
      (node (ref "E22") (pin "13") (pinfunction "I1_13") (pintype "input"))
      (node (ref "E22") (pin "3") (pinfunction "O_3") (pintype "output"))
    )
    (net (code "43") (name "DF_DB00") (class "Default")
      (node (ref "E16") (pin "14") (pinfunction "I3_14") (pintype "input"))
      (node (ref "E17") (pin "14") (pinfunction "O_14") (pintype "output"))
      (node (ref "E34") (pin "12") (pinfunction "D_12") (pintype "input"))
      (node (ref "E42") (pin "9") (pinfunction "I1_9") (pintype "input"))
    )
    (net (code "44") (name "DF_DB01") (class "Default")
      (node (ref "E11") (pin "14") (pinfunction "I3_14") (pintype "input"))
      (node (ref "E12") (pin "14") (pinfunction "O_14") (pintype "output"))
      (node (ref "E18") (pin "2") (pinfunction "I1_2") (pintype "input"))
      (node (ref "E34") (pin "2") (pinfunction "D_2") (pintype "input"))
    )
    (net (code "45") (name "DF_DB02") (class "Default")
      (node (ref "E06") (pin "14") (pinfunction "I3_14") (pintype "input"))
      (node (ref "E07") (pin "14") (pinfunction "O_14") (pintype "output"))
      (node (ref "E30") (pin "2") (pinfunction "D_2") (pintype "input"))
      (node (ref "E42") (pin "13") (pinfunction "I1_13") (pintype "input"))
    )
    (net (code "46") (name "DF_DB03") (class "Default")
      (node (ref "E16") (pin "15") (pinfunction "I2_15") (pintype "input"))
      (node (ref "E17") (pin "13") (pinfunction "O_13") (pintype "output"))
      (node (ref "E30") (pin "12") (pinfunction "D_12") (pintype "input"))
    )
    (net (code "47") (name "DF_SEL_ER") (class "Default")
      (node (ref "E32") (pin "12") (pinfunction "O_12") (pintype "output"))
      (node (ref "E37") (pin "6") (pinfunction "I1_6") (pintype "input"))
    )
    (net (code "48") (name "DF_TIME_ER") (class "Default")
      (node (ref "E27") (pin "13") (pinfunction "I2_13") (pintype "input"))
      (node (ref "E35") (pin "6") (pinfunction "O_6") (pintype "output"))
      (node (ref "E37") (pin "5") (pinfunction "I0_5") (pintype "input"))
      (node (ref "E41") (pin "2") (pinfunction "I0_2") (pintype "input"))
    )
    (net (code "49") (name "F{slash}~{R}") (class "Default")
      (node (ref "E39") (pin "8") (pinfunction "O_8") (pintype "open_collector"))
      (node (ref "J1") (pin "TT") (pinfunction "38_TT") (pintype "bidirectional"))
    )
    (net (code "50") (name "GND") (class "Default")
      (node (ref "C1") (pin "2") (pinfunction "2_2") (pintype "passive"))
      (node (ref "C10") (pin "2") (pinfunction "2_2") (pintype "passive"))
      (node (ref "C11") (pin "2") (pinfunction "2_2") (pintype "passive"))
      (node (ref "C12") (pin "2") (pinfunction "2_2") (pintype "passive"))
      (node (ref "C13") (pin "2") (pinfunction "2_2") (pintype "passive"))
      (node (ref "C14") (pin "2") (pinfunction "2_2") (pintype "passive"))
      (node (ref "C15") (pin "2") (pinfunction "2_2") (pintype "passive"))
      (node (ref "C16") (pin "2") (pinfunction "2_2") (pintype "passive"))
      (node (ref "C17") (pin "2") (pinfunction "2_2") (pintype "passive"))
      (node (ref "C18") (pin "2") (pinfunction "2_2") (pintype "passive"))
      (node (ref "C19") (pin "2") (pinfunction "2_2") (pintype "passive"))
      (node (ref "C2") (pin "2") (pinfunction "2_2") (pintype "passive"))
      (node (ref "C20") (pin "2") (pinfunction "2_2") (pintype "passive"))
      (node (ref "C21") (pin "2") (pinfunction "2_2") (pintype "passive"))
      (node (ref "C22") (pin "2") (pinfunction "2_2") (pintype "passive"))
      (node (ref "C23") (pin "2") (pinfunction "2_2") (pintype "passive"))
      (node (ref "C24") (pin "2") (pinfunction "2_2") (pintype "passive"))
      (node (ref "C25") (pin "2") (pinfunction "2_2") (pintype "passive"))
      (node (ref "C26") (pin "2") (pinfunction "2_2") (pintype "passive"))
      (node (ref "C27") (pin "2") (pinfunction "2_2") (pintype "passive"))
      (node (ref "C28") (pin "2") (pinfunction "2_2") (pintype "passive"))
      (node (ref "C29") (pin "2") (pinfunction "2_2") (pintype "passive"))
      (node (ref "C3") (pin "2") (pinfunction "2_2") (pintype "passive"))
      (node (ref "C30") (pin "2") (pinfunction "2_2") (pintype "passive"))
      (node (ref "C31") (pin "2") (pinfunction "2_2") (pintype "passive"))
      (node (ref "C32") (pin "2") (pinfunction "2_2") (pintype "passive"))
      (node (ref "C33") (pin "2") (pinfunction "2_2") (pintype "passive"))
      (node (ref "C34") (pin "-") (pinfunction "-_-") (pintype "passive"))
      (node (ref "C35") (pin "-") (pinfunction "-_-") (pintype "passive"))
      (node (ref "C4") (pin "2") (pinfunction "2_2") (pintype "passive"))
      (node (ref "C40") (pin "2") (pinfunction "2_2") (pintype "passive"))
      (node (ref "C41") (pin "1") (pinfunction "1_1") (pintype "passive"))
      (node (ref "C42") (pin "1") (pinfunction "1_1") (pintype "passive"))
      (node (ref "C43") (pin "2") (pinfunction "2_2") (pintype "passive"))
      (node (ref "C44") (pin "1") (pinfunction "1_1") (pintype "passive"))
      (node (ref "C45") (pin "2") (pinfunction "2_2") (pintype "passive"))
      (node (ref "C46") (pin "-") (pinfunction "-_-") (pintype "passive"))
      (node (ref "C47") (pin "2") (pinfunction "2_2") (pintype "passive"))
      (node (ref "C48") (pin "1") (pinfunction "1_1") (pintype "passive"))
      (node (ref "C5") (pin "2") (pinfunction "2_2") (pintype "passive"))
      (node (ref "C6") (pin "2") (pinfunction "2_2") (pintype "passive"))
      (node (ref "C7") (pin "2") (pinfunction "2_2") (pintype "passive"))
      (node (ref "C8") (pin "2") (pinfunction "2_2") (pintype "passive"))
      (node (ref "C9") (pin "2") (pinfunction "2_2") (pintype "passive"))
      (node (ref "D2") (pin "A") (pinfunction "A_A") (pintype "passive"))
      (node (ref "E04") (pin "1") (pinfunction "A_1") (pintype "input"))
      (node (ref "E08") (pin "1") (pinfunction "A_1") (pintype "input"))
      (node (ref "E08") (pin "9") (pinfunction "A_9") (pintype "input"))
      (node (ref "E20") (pin "10") (pinfunction "I1_10") (pintype "input"))
      (node (ref "E20") (pin "12") (pinfunction "I1_12") (pintype "input"))
      (node (ref "E25") (pin "7") (pinfunction "7_7") (pintype "passive"))
      (node (ref "E28") (pin "10") (pinfunction "I1_10") (pintype "input"))
      (node (ref "E28") (pin "4") (pinfunction "I0_4") (pintype "input"))
      (node (ref "E28") (pin "7") (pinfunction "I1_7") (pintype "input"))
      (node (ref "EDGE$") (pin "AC2") (pinfunction "1_AC2") (pintype "bidirectional"))
      (node (ref "EDGE$") (pin "AF1") (pinfunction "1_AF1") (pintype "bidirectional"))
      (node (ref "EDGE$") (pin "AF2") (pinfunction "1_AF2") (pintype "bidirectional"))
      (node (ref "EDGE$") (pin "AN1") (pinfunction "1_AN1") (pintype "bidirectional"))
      (node (ref "EDGE$") (pin "AN2") (pinfunction "1_AN2") (pintype "bidirectional"))
      (node (ref "EDGE$") (pin "AT1") (pinfunction "1_AT1") (pintype "bidirectional"))
      (node (ref "EDGE$") (pin "AT2") (pinfunction "1_AT2") (pintype "bidirectional"))
      (node (ref "EDGE$") (pin "BC1") (pinfunction "1_BC1") (pintype "bidirectional"))
      (node (ref "EDGE$") (pin "BC2") (pinfunction "1_BC2") (pintype "bidirectional"))
      (node (ref "EDGE$") (pin "BF1") (pinfunction "1_BF1") (pintype "bidirectional"))
      (node (ref "EDGE$") (pin "BF2") (pinfunction "1_BF2") (pintype "bidirectional"))
      (node (ref "EDGE$") (pin "BN2") (pinfunction "1_BN2") (pintype "bidirectional"))
      (node (ref "EDGE$") (pin "BT1") (pinfunction "1_BT1") (pintype "bidirectional"))
      (node (ref "EDGE$") (pin "BT2") (pinfunction "1_BT2") (pintype "bidirectional"))
      (node (ref "EDGE$") (pin "CC1") (pinfunction "1_CC1") (pintype "bidirectional"))
      (node (ref "EDGE$") (pin "CC2") (pinfunction "1_CC2") (pintype "bidirectional"))
      (node (ref "EDGE$") (pin "CF1") (pinfunction "1_CF1") (pintype "bidirectional"))
      (node (ref "EDGE$") (pin "CF2") (pinfunction "1_CF2") (pintype "bidirectional"))
      (node (ref "EDGE$") (pin "CN1") (pinfunction "1_CN1") (pintype "bidirectional"))
      (node (ref "EDGE$") (pin "CN2") (pinfunction "1_CN2") (pintype "bidirectional"))
      (node (ref "EDGE$") (pin "CT1") (pinfunction "1_CT1") (pintype "bidirectional"))
      (node (ref "EDGE$") (pin "CT2") (pinfunction "1_CT2") (pintype "bidirectional"))
      (node (ref "EDGE$") (pin "DC1") (pinfunction "1_DC1") (pintype "bidirectional"))
      (node (ref "EDGE$") (pin "DC2") (pinfunction "1_DC2") (pintype "bidirectional"))
      (node (ref "EDGE$") (pin "DF1") (pinfunction "1_DF1") (pintype "bidirectional"))
      (node (ref "EDGE$") (pin "DF2") (pinfunction "1_DF2") (pintype "bidirectional"))
      (node (ref "EDGE$") (pin "DN1") (pinfunction "1_DN1") (pintype "bidirectional"))
      (node (ref "EDGE$") (pin "DN2") (pinfunction "1_DN2") (pintype "bidirectional"))
      (node (ref "EDGE$") (pin "DT1") (pinfunction "1_DT1") (pintype "bidirectional"))
      (node (ref "EDGE$") (pin "DT2") (pinfunction "1_DT2") (pintype "bidirectional"))
      (node (ref "J1") (pin "A") (pinfunction "1_A") (pintype "bidirectional"))
      (node (ref "J1") (pin "AA") (pinfunction "23_AA") (pintype "bidirectional"))
      (node (ref "J1") (pin "B") (pinfunction "2_B") (pintype "bidirectional"))
      (node (ref "J1") (pin "C") (pinfunction "3_C") (pintype "bidirectional"))
      (node (ref "J1") (pin "CC") (pinfunction "25_CC") (pintype "bidirectional"))
      (node (ref "J1") (pin "E") (pinfunction "5_E") (pintype "bidirectional"))
      (node (ref "J1") (pin "EE") (pinfunction "27_EE") (pintype "bidirectional"))
      (node (ref "J1") (pin "H") (pinfunction "7_H") (pintype "bidirectional"))
      (node (ref "J1") (pin "HH") (pinfunction "29_HH") (pintype "bidirectional"))
      (node (ref "J1") (pin "K") (pinfunction "9_K") (pintype "bidirectional"))
      (node (ref "J1") (pin "KK") (pinfunction "31_KK") (pintype "bidirectional"))
      (node (ref "J1") (pin "M") (pinfunction "11_M") (pintype "bidirectional"))
      (node (ref "J1") (pin "MM") (pinfunction "33_MM") (pintype "bidirectional"))
      (node (ref "J1") (pin "P") (pinfunction "13_P") (pintype "bidirectional"))
      (node (ref "J1") (pin "PP") (pinfunction "35_PP") (pintype "bidirectional"))
      (node (ref "J1") (pin "S") (pinfunction "15_S") (pintype "bidirectional"))
      (node (ref "J1") (pin "SS") (pinfunction "37_SS") (pintype "bidirectional"))
      (node (ref "J1") (pin "U") (pinfunction "17_U") (pintype "bidirectional"))
      (node (ref "J1") (pin "UU") (pinfunction "39_UU") (pintype "bidirectional"))
      (node (ref "J1") (pin "VV") (pinfunction "40_VV") (pintype "bidirectional"))
      (node (ref "J1") (pin "W") (pinfunction "19_W") (pintype "bidirectional"))
      (node (ref "J1") (pin "Y") (pinfunction "21_Y") (pintype "bidirectional"))
      (node (ref "Q4") (pin "3") (pinfunction "C_3") (pintype "passive"))
      (node (ref "Q5") (pin "3") (pinfunction "C_3") (pintype "passive"))
      (node (ref "R36") (pin "2") (pinfunction "2_2") (pintype "passive"))
      (node (ref "R37") (pin "2") (pinfunction "2_2") (pintype "passive"))
      (node (ref "WTM") (pin "2") (pinfunction "S_2") (pintype "passive"))
    )
    (net (code "51") (name "INITIALIZE") (class "Default")
      (node (ref "E28") (pin "5") (pinfunction "I1_5") (pintype "input"))
      (node (ref "EDGE$") (pin "CR1") (pinfunction "1_CR1") (pintype "bidirectional"))
    )
    (net (code "52") (name "INTERNAL_IO") (class "Default")
      (node (ref "E33") (pin "4") (pinfunction "O_4") (pintype "open_collector"))
      (node (ref "EDGE$") (pin "CL1") (pinfunction "1_CL1") (pintype "bidirectional"))
    )
    (net (code "53") (name "IO_PAUSE") (class "Default")
      (node (ref "E28") (pin "9") (pinfunction "I0_9") (pintype "input"))
      (node (ref "EDGE$") (pin "CD1") (pinfunction "1_CD1") (pintype "bidirectional"))
    )
    (net (code "54") (name "MD03") (class "Default")
      (node (ref "E24") (pin "9") (pinfunction "I3_9") (pintype "input"))
      (node (ref "EDGE$") (pin "AP1") (pinfunction "1_AP1") (pintype "bidirectional"))
    )
    (net (code "55") (name "MD04") (class "Default")
      (node (ref "E24") (pin "4") (pinfunction "I0_4") (pintype "input"))
      (node (ref "EDGE$") (pin "BK1") (pinfunction "1_BK1") (pintype "bidirectional"))
    )
    (net (code "56") (name "MD05") (class "Default")
      (node (ref "E24") (pin "5") (pinfunction "I1_5") (pintype "input"))
      (node (ref "EDGE$") (pin "BL1") (pinfunction "1_BL1") (pintype "bidirectional"))
    )
    (net (code "57") (name "MD06") (class "Default")
      (node (ref "E24") (pin "6") (pinfunction "I2_6") (pintype "input"))
      (node (ref "EDGE$") (pin "BM1") (pinfunction "1_BM1") (pintype "bidirectional"))
    )
    (net (code "58") (name "MD07") (class "Default")
      (node (ref "E20") (pin "5") (pinfunction "I1_5") (pintype "input"))
      (node (ref "EDGE$") (pin "BP1") (pinfunction "1_BP1") (pintype "bidirectional"))
      (node (ref "W2W1") (pin "1") (pinfunction "1_1") (pintype "passive"))
    )
    (net (code "59") (name "MD08") (class "Default")
      (node (ref "E20") (pin "6") (pinfunction "I0_6") (pintype "input"))
      (node (ref "EDGE$") (pin "DK1") (pinfunction "1_DK1") (pintype "bidirectional"))
      (node (ref "W4W3") (pin "1") (pinfunction "1_1") (pintype "passive"))
    )
    (net (code "60") (name "MD09") (class "Default")
      (node (ref "E44") (pin "7") (pinfunction "I1_7") (pintype "input"))
      (node (ref "EDGE$") (pin "DL1") (pinfunction "1_DL1") (pintype "bidirectional"))
    )
    (net (code "61") (name "MD10") (class "Default")
      (node (ref "E44") (pin "9") (pinfunction "I0_9") (pintype "input"))
      (node (ref "EDGE$") (pin "DM1") (pinfunction "1_DM1") (pintype "bidirectional"))
    )
    (net (code "62") (name "MD11") (class "Default")
      (node (ref "E28") (pin "12") (pinfunction "I1_12") (pintype "input"))
      (node (ref "E44") (pin "11") (pinfunction "I0_11") (pintype "input"))
      (node (ref "EDGE$") (pin "DP1") (pinfunction "1_DP1") (pintype "bidirectional"))
    )
    (net (code "63") (name "N$36") (class "Default")
      (node (ref "E36") (pin "11") (pinfunction "QD_11") (pintype "output"))
      (node (ref "E37") (pin "3") (pinfunction "I1_3") (pintype "input"))
      (node (ref "E41") (pin "12") (pinfunction "I1_12") (pintype "input"))
    )
    (net (code "64") (name "ND0") (class "Default")
      (node (ref "E39") (pin "12") (pinfunction "O_12") (pintype "open_collector"))
      (node (ref "J1") (pin "FF") (pinfunction "28_FF") (pintype "bidirectional"))
    )
    (net (code "65") (name "ND1") (class "Default")
      (node (ref "E39") (pin "4") (pinfunction "O_4") (pintype "open_collector"))
      (node (ref "J1") (pin "DD") (pinfunction "26_DD") (pintype "bidirectional"))
    )
    (net (code "66") (name "ND2") (class "Default")
      (node (ref "E39") (pin "2") (pinfunction "O_2") (pintype "open_collector"))
      (node (ref "J1") (pin "X") (pinfunction "20_X") (pintype "bidirectional"))
    )
    (net (code "67") (name "Net-(D2-PadC)") (class "Default")
      (node (ref "D2") (pin "C") (pinfunction "C_C") (pintype "passive"))
      (node (ref "D3") (pin "A") (pinfunction "A_A") (pintype "passive"))
    )
    (net (code "68") (name "Net-(D4-PadC)") (class "Default")
      (node (ref "D4") (pin "C") (pinfunction "C_C") (pintype "passive"))
      (node (ref "D6") (pin "A") (pinfunction "A_A") (pintype "passive"))
    )
    (net (code "69") (name "Net-(D7-PadC)") (class "Default")
      (node (ref "D7") (pin "C") (pinfunction "C_C") (pintype "passive"))
      (node (ref "D8") (pin "C") (pinfunction "C_C") (pintype "passive"))
      (node (ref "R39") (pin "2") (pinfunction "2_2") (pintype "passive"))
    )
    (net (code "70") (name "Net-(D10-PadC)") (class "Default")
      (node (ref "D10") (pin "C") (pinfunction "C_C") (pintype "passive"))
      (node (ref "D9") (pin "C") (pinfunction "C_C") (pintype "passive"))
      (node (ref "R40") (pin "2") (pinfunction "2_2") (pintype "passive"))
    )
    (net (code "71") (name "Net-(E01F-O)") (class "Default")
      (node (ref "E01") (pin "12") (pinfunction "O_12") (pintype "output"))
      (node (ref "R25") (pin "2") (pinfunction "2_2") (pintype "passive"))
    )
    (net (code "72") (name "Net-(E02A-O)") (class "Default")
      (node (ref "E02") (pin "1") (pinfunction "O_1") (pintype "output"))
      (node (ref "E31") (pin "9") (pinfunction "I_9") (pintype "input"))
    )
    (net (code "73") (name "Net-(E02B-I0)") (class "Default")
      (node (ref "E02") (pin "5") (pinfunction "I0_5") (pintype "input"))
      (node (ref "E03") (pin "6") (pinfunction "~{Q}_6") (pintype "output"))
      (node (ref "E04") (pin "2") (pinfunction "B_2") (pintype "input"))
    )
    (net (code "74") (name "Net-(E02B-O)") (class "Default")
      (node (ref "E02") (pin "4") (pinfunction "O_4") (pintype "output"))
      (node (ref "E03") (pin "12") (pinfunction "D_12") (pintype "input"))
      (node (ref "E03") (pin "13") (pinfunction "CLR_13") (pintype "input"))
    )
    (net (code "75") (name "Net-(E02C-I0)") (class "Default")
      (node (ref "E02") (pin "8") (pinfunction "I0_8") (pintype "input"))
      (node (ref "E38") (pin "12") (pinfunction "I0_12") (pintype "input"))
      (node (ref "E38") (pin "8") (pinfunction "O_8") (pintype "output"))
    )
    (net (code "76") (name "Net-(E02C-O)") (class "Default")
      (node (ref "E02") (pin "10") (pinfunction "O_10") (pintype "output"))
      (node (ref "E46") (pin "8") (pinfunction "I0_8") (pintype "input"))
    )
    (net (code "77") (name "Net-(E02D-O)") (class "Default")
      (node (ref "E02") (pin "13") (pinfunction "O_13") (pintype "output"))
      (node (ref "E09") (pin "2") (pinfunction "D_2") (pintype "input"))
    )
    (net (code "78") (name "Net-(E03A-CLK)") (class "Default")
      (node (ref "E03") (pin "3") (pinfunction "CLK_3") (pintype "input"))
      (node (ref "E26") (pin "5") (pinfunction "I_5") (pintype "input"))
      (node (ref "E30") (pin "11") (pinfunction "CLK_11") (pintype "input"))
      (node (ref "E30") (pin "3") (pinfunction "CLK_3") (pintype "input"))
      (node (ref "E34") (pin "11") (pinfunction "CLK_11") (pintype "input"))
      (node (ref "E34") (pin "3") (pinfunction "CLK_3") (pintype "input"))
      (node (ref "E37") (pin "13") (pinfunction "O_13") (pintype "output"))
    )
    (net (code "79") (name "Net-(E03A-CLR)") (class "Default")
      (node (ref "E03") (pin "1") (pinfunction "CLR_1") (pintype "input"))
      (node (ref "E04") (pin "3") (pinfunction "CLR_3") (pintype "input"))
      (node (ref "R42") (pin "2") (pinfunction "2_2") (pintype "passive"))
    )
    (net (code "80") (name "Net-(E03A-D)") (class "Default")
      (node (ref "E03") (pin "2") (pinfunction "D_2") (pintype "input"))
      (node (ref "E18") (pin "3") (pinfunction "O_3") (pintype "open_collector"))
      (node (ref "E42") (pin "10") (pinfunction "O_10") (pintype "open_collector"))
      (node (ref "E42") (pin "11") (pinfunction "O_11") (pintype "open_collector"))
      (node (ref "R15") (pin "1") (pinfunction "1_1") (pintype "passive"))
    )
    (net (code "81") (name "Net-(E03A-PRE)") (class "Default")
      (node (ref "E03") (pin "4") (pinfunction "PRE_4") (pintype "input"))
      (node (ref "E43") (pin "12") (pinfunction "I1_12") (pintype "input"))
      (node (ref "E44") (pin "3") (pinfunction "O_3") (pintype "output"))
    )
    (net (code "82") (name "Net-(E03B-CLK)") (class "Default")
      (node (ref "E03") (pin "11") (pinfunction "CLK_11") (pintype "input"))
      (node (ref "E04") (pin "4") (pinfunction "~{Q}_4") (pintype "output"))
    )
    (net (code "83") (name "Net-(E04A-C)") (class "Default")
      (node (ref "C36") (pin "-") (pinfunction "-_-") (pintype "passive"))
      (node (ref "E04") (pin "14") (pinfunction "C_14") (pintype "input"))
    )
    (net (code "84") (name "Net-(E04A-R{slash}C)") (class "Default")
      (node (ref "C36") (pin "+") (pinfunction "+_+") (pintype "passive"))
      (node (ref "E04") (pin "15") (pinfunction "R/C_15") (pintype "input"))
      (node (ref "R17") (pin "1") (pinfunction "1_1") (pintype "passive"))
    )
    (net (code "85") (name "Net-(E04B-C)") (class "Default")
      (node (ref "C39") (pin "2") (pinfunction "2_2") (pintype "passive"))
      (node (ref "E04") (pin "6") (pinfunction "C_6") (pintype "input"))
    )
    (net (code "86") (name "Net-(E04B-R{slash}C)") (class "Default")
      (node (ref "C39") (pin "1") (pinfunction "1_1") (pintype "passive"))
      (node (ref "E04") (pin "7") (pinfunction "R/C_7") (pintype "input"))
      (node (ref "R43") (pin "1") (pinfunction "1_1") (pintype "passive"))
    )
    (net (code "87") (name "Net-(E06A-C)") (class "Default")
      (node (ref "E06") (pin "6") (pinfunction "C_6") (pintype "input"))
      (node (ref "E11") (pin "6") (pinfunction "C_6") (pintype "input"))
      (node (ref "E16") (pin "6") (pinfunction "C_6") (pintype "input"))
      (node (ref "E26") (pin "8") (pinfunction "O_8") (pintype "output"))
    )
    (net (code "88") (name "Net-(E06A-I0)") (class "Default")
      (node (ref "E06") (pin "3") (pinfunction "I0_3") (pintype "input"))
      (node (ref "E07") (pin "2") (pinfunction "O_2") (pintype "output"))
    )
    (net (code "89") (name "Net-(E06A-I1)") (class "Default")
      (node (ref "E06") (pin "2") (pinfunction "I1_2") (pintype "input"))
      (node (ref "E07") (pin "3") (pinfunction "O_3") (pintype "output"))
    )
    (net (code "90") (name "Net-(E06A-I2)") (class "Default")
      (node (ref "E06") (pin "15") (pinfunction "I2_15") (pintype "input"))
      (node (ref "E07") (pin "13") (pinfunction "O_13") (pintype "output"))
    )
    (net (code "91") (name "Net-(E06A-L)") (class "Default")
      (node (ref "E06") (pin "1") (pinfunction "R_1") (pintype "input"))
      (node (ref "E06") (pin "10") (pinfunction "L_10") (pintype "input"))
      (node (ref "E11") (pin "1") (pinfunction "R_1") (pintype "input"))
      (node (ref "E11") (pin "10") (pinfunction "L_10") (pintype "input"))
      (node (ref "E16") (pin "1") (pinfunction "R_1") (pintype "input"))
      (node (ref "E16") (pin "10") (pinfunction "L_10") (pintype "input"))
      (node (ref "R3") (pin "1") (pinfunction "1_1") (pintype "passive"))
    )
    (net (code "92") (name "Net-(E08A-B)") (class "Default")
      (node (ref "E08") (pin "2") (pinfunction "B_2") (pintype "input"))
      (node (ref "E08") (pin "5") (pinfunction "Q_5") (pintype "output"))
    )
    (net (code "93") (name "Net-(E08A-C)") (class "Default")
      (node (ref "C38") (pin "2") (pinfunction "2_2") (pintype "passive"))
      (node (ref "E08") (pin "14") (pinfunction "C_14") (pintype "input"))
    )
    (net (code "94") (name "Net-(E08A-CLR)") (class "Default")
      (node (ref "E08") (pin "11") (pinfunction "CLR_11") (pintype "input"))
      (node (ref "E08") (pin "3") (pinfunction "CLR_3") (pintype "input"))
      (node (ref "E09") (pin "10") (pinfunction "PRE_10") (pintype "input"))
      (node (ref "E09") (pin "13") (pinfunction "CLR_13") (pintype "input"))
      (node (ref "E09") (pin "4") (pinfunction "PRE_4") (pintype "input"))
      (node (ref "E14") (pin "1") (pinfunction "CLR_1") (pintype "input"))
      (node (ref "E14") (pin "10") (pinfunction "PRE_10") (pintype "input"))
      (node (ref "E14") (pin "13") (pinfunction "CLR_13") (pintype "input"))
      (node (ref "E14") (pin "4") (pinfunction "PRE_4") (pintype "input"))
      (node (ref "R22") (pin "2") (pinfunction "2_2") (pintype "passive"))
    )
    (net (code "95") (name "Net-(E08A-R{slash}C)") (class "Default")
      (node (ref "C38") (pin "1") (pinfunction "1_1") (pintype "passive"))
      (node (ref "E08") (pin "15") (pinfunction "R/C_15") (pintype "input"))
      (node (ref "R24") (pin "1") (pinfunction "1_1") (pintype "passive"))
    )
    (net (code "96") (name "Net-(E08B-C)") (class "Default")
      (node (ref "C37") (pin "2") (pinfunction "2_2") (pintype "passive"))
      (node (ref "E08") (pin "6") (pinfunction "C_6") (pintype "input"))
    )
    (net (code "97") (name "Net-(E08B-R{slash}C)") (class "Default")
      (node (ref "C37") (pin "1") (pinfunction "1_1") (pintype "passive"))
      (node (ref "E08") (pin "7") (pinfunction "R/C_7") (pintype "input"))
      (node (ref "R23") (pin "1") (pinfunction "1_1") (pintype "passive"))
    )
    (net (code "98") (name "Net-(E08B-~{Q})") (class "Default")
      (node (ref "E08") (pin "12") (pinfunction "~{Q}_12") (pintype "output"))
      (node (ref "E09") (pin "11") (pinfunction "CLK_11") (pintype "input"))
      (node (ref "E09") (pin "3") (pinfunction "CLK_3") (pintype "input"))
      (node (ref "E19") (pin "9") (pinfunction "I0_9") (pintype "input"))
    )
    (net (code "99") (name "Net-(E09A-Q)") (class "Default")
      (node (ref "E09") (pin "5") (pinfunction "Q_5") (pintype "output"))
      (node (ref "E23") (pin "9") (pinfunction "I0_9") (pintype "input"))
      (node (ref "E27") (pin "9") (pinfunction "I0_9") (pintype "input"))
    )
    (net (code "100") (name "Net-(E09B-D)") (class "Default")
      (node (ref "E09") (pin "12") (pinfunction "D_12") (pintype "input"))
      (node (ref "E09") (pin "8") (pinfunction "~{Q}_8") (pintype "output"))
      (node (ref "E23") (pin "11") (pinfunction "I2_11") (pintype "input"))
    )
    (net (code "101") (name "Net-(E10A-B3)") (class "Default")
      (node (ref "E10") (pin "14") (pinfunction "B3_14") (pintype "input"))
      (node (ref "E37") (pin "4") (pinfunction "O_4") (pintype "output"))
    )
    (net (code "102") (name "Net-(E11A-I0)") (class "Default")
      (node (ref "E11") (pin "3") (pinfunction "I0_3") (pintype "input"))
      (node (ref "E12") (pin "2") (pinfunction "O_2") (pintype "output"))
    )
    (net (code "103") (name "Net-(E11A-I1)") (class "Default")
      (node (ref "E11") (pin "2") (pinfunction "I1_2") (pintype "input"))
      (node (ref "E12") (pin "3") (pinfunction "O_3") (pintype "output"))
    )
    (net (code "104") (name "Net-(E11A-I2)") (class "Default")
      (node (ref "E11") (pin "15") (pinfunction "I2_15") (pintype "input"))
      (node (ref "E12") (pin "13") (pinfunction "O_13") (pintype "output"))
    )
    (net (code "105") (name "Net-(E13A-C12)") (class "Default")
      (node (ref "E13") (pin "13") (pinfunction "C12_13") (pintype "input"))
      (node (ref "E13") (pin "4") (pinfunction "C34_4") (pintype "input"))
      (node (ref "E31") (pin "12") (pinfunction "O_12") (pintype "output"))
    )
    (net (code "106") (name "Net-(E13A-~{Q1})") (class "Default")
      (node (ref "E13") (pin "1") (pinfunction "~{Q1}_1") (pintype "output"))
      (node (ref "E18") (pin "13") (pinfunction "I1_13") (pintype "input"))
    )
    (net (code "107") (name "Net-(E13A-~{Q3})") (class "Default")
      (node (ref "E13") (pin "11") (pinfunction "~{Q3}_11") (pintype "output"))
      (node (ref "E18") (pin "6") (pinfunction "I1_6") (pintype "input"))
    )
    (net (code "108") (name "Net-(E13A-~{Q4})") (class "Default")
      (node (ref "E13") (pin "8") (pinfunction "~{Q4}_8") (pintype "output"))
      (node (ref "E18") (pin "8") (pinfunction "I0_8") (pintype "input"))
    )
    (net (code "109") (name "Net-(E14A-D)") (class "Default")
      (node (ref "E14") (pin "2") (pinfunction "D_2") (pintype "input"))
      (node (ref "E14") (pin "8") (pinfunction "~{Q}_8") (pintype "output"))
      (node (ref "E23") (pin "3") (pinfunction "I0_3") (pintype "input"))
      (node (ref "E39") (pin "5") (pinfunction "I_5") (pintype "input"))
    )
    (net (code "110") (name "Net-(E16A-I0)") (class "Default")
      (node (ref "E16") (pin "3") (pinfunction "I0_3") (pintype "input"))
      (node (ref "E17") (pin "2") (pinfunction "O_2") (pintype "output"))
    )
    (net (code "111") (name "Net-(E16A-I1)") (class "Default")
      (node (ref "E16") (pin "2") (pinfunction "I1_2") (pintype "input"))
      (node (ref "E17") (pin "3") (pinfunction "O_3") (pintype "output"))
    )
    (net (code "112") (name "Net-(E18B-O)") (class "Default")
      (node (ref "E18") (pin "4") (pinfunction "O_4") (pintype "open_collector"))
      (node (ref "E39") (pin "13") (pinfunction "I_13") (pintype "input"))
      (node (ref "R10") (pin "1") (pinfunction "1_1") (pintype "passive"))
    )
    (net (code "113") (name "Net-(E18C-O)") (class "Default")
      (node (ref "E18") (pin "10") (pinfunction "O_10") (pintype "open_collector"))
      (node (ref "E39") (pin "3") (pinfunction "I_3") (pintype "input"))
      (node (ref "R9") (pin "1") (pinfunction "1_1") (pintype "passive"))
    )
    (net (code "114") (name "Net-(E18D-O)") (class "Default")
      (node (ref "E18") (pin "11") (pinfunction "O_11") (pintype "open_collector"))
      (node (ref "E39") (pin "1") (pinfunction "I_1") (pintype "input"))
      (node (ref "R8") (pin "1") (pinfunction "1_1") (pintype "passive"))
    )
    (net (code "115") (name "Net-(E19A-I0)") (class "Default")
      (node (ref "E19") (pin "1") (pinfunction "I0_1") (pintype "input"))
      (node (ref "E23") (pin "8") (pinfunction "O_8") (pintype "output"))
    )
    (net (code "116") (name "Net-(E19A-I1)") (class "Default")
      (node (ref "E19") (pin "2") (pinfunction "I1_2") (pintype "input"))
      (node (ref "E23") (pin "12") (pinfunction "O_12") (pintype "output"))
    )
    (net (code "117") (name "Net-(E19B-I0)") (class "Default")
      (node (ref "E19") (pin "4") (pinfunction "I0_4") (pintype "input"))
      (node (ref "E27") (pin "8") (pinfunction "O_8") (pintype "output"))
    )
    (net (code "118") (name "Net-(E19B-I1)") (class "Default")
      (node (ref "E19") (pin "5") (pinfunction "I1_5") (pintype "input"))
      (node (ref "E23") (pin "6") (pinfunction "O_6") (pintype "output"))
    )
    (net (code "119") (name "Net-(E19C-I1)") (class "Default")
      (node (ref "E19") (pin "10") (pinfunction "I1_10") (pintype "input"))
      (node (ref "E43") (pin "1") (pinfunction "O_1") (pintype "open_collector"))
      (node (ref "E43") (pin "4") (pinfunction "O_4") (pintype "open_collector"))
      (node (ref "R21") (pin "1") (pinfunction "1_1") (pintype "passive"))
    )
    (net (code "120") (name "Net-(E19D-I0)") (class "Default")
      (node (ref "E19") (pin "12") (pinfunction "I0_12") (pintype "input"))
      (node (ref "E26") (pin "1") (pinfunction "I_1") (pintype "input"))
      (node (ref "E40") (pin "8") (pinfunction "O_8") (pintype "output"))
    )
    (net (code "121") (name "Net-(E19D-O)") (class "Default")
      (node (ref "E19") (pin "11") (pinfunction "O_11") (pintype "output"))
      (node (ref "E30") (pin "13") (pinfunction "CLR_13") (pintype "input"))
    )
    (net (code "122") (name "Net-(E20A-I0)") (class "Default")
      (node (ref "E20") (pin "4") (pinfunction "I0_4") (pintype "input"))
      (node (ref "E20") (pin "7") (pinfunction "I1_7") (pintype "input"))
      (node (ref "E24") (pin "10") (pinfunction "I4_10") (pintype "input"))
      (node (ref "E28") (pin "14") (pinfunction "O_14") (pintype "output"))
    )
    (net (code "123") (name "Net-(E20A-O)") (class "Default")
      (node (ref "E20") (pin "3") (pinfunction "O_3") (pintype "output"))
      (node (ref "W2W1") (pin "3") (pinfunction "3_3") (pintype "passive"))
    )
    (net (code "124") (name "Net-(E20B-O)") (class "Default")
      (node (ref "E20") (pin "2") (pinfunction "O_2") (pintype "output"))
      (node (ref "W4W3") (pin "3") (pinfunction "3_3") (pintype "passive"))
    )
    (net (code "125") (name "Net-(E21A-C)") (class "Default")
      (node (ref "E21") (pin "6") (pinfunction "C_6") (pintype "input"))
      (node (ref "E22") (pin "6") (pinfunction "O_6") (pintype "output"))
      (node (ref "E29") (pin "6") (pinfunction "C_6") (pintype "input"))
    )
    (net (code "126") (name "Net-(E21A-I0)") (class "Default")
      (node (ref "E21") (pin "1") (pinfunction "R_1") (pintype "input"))
      (node (ref "E21") (pin "10") (pinfunction "L_10") (pintype "input"))
      (node (ref "E21") (pin "14") (pinfunction "I3_14") (pintype "input"))
      (node (ref "E21") (pin "15") (pinfunction "I2_15") (pintype "input"))
      (node (ref "E21") (pin "2") (pinfunction "I1_2") (pintype "input"))
      (node (ref "E21") (pin "3") (pinfunction "I0_3") (pintype "input"))
      (node (ref "E29") (pin "1") (pinfunction "R_1") (pintype "input"))
      (node (ref "E29") (pin "10") (pinfunction "L_10") (pintype "input"))
      (node (ref "E29") (pin "14") (pinfunction "I3_14") (pintype "input"))
      (node (ref "E29") (pin "15") (pinfunction "I2_15") (pintype "input"))
      (node (ref "E29") (pin "2") (pinfunction "I1_2") (pintype "input"))
      (node (ref "E29") (pin "3") (pinfunction "I0_3") (pintype "input"))
      (node (ref "R2") (pin "1") (pinfunction "1_1") (pintype "passive"))
    )
    (net (code "127") (name "Net-(E22A-I0)") (class "Default")
      (node (ref "E22") (pin "1") (pinfunction "I0_1") (pintype "input"))
      (node (ref "E22") (pin "11") (pinfunction "O_11") (pintype "output"))
    )
    (net (code "128") (name "Net-(E22C-I1)") (class "Default")
      (node (ref "E22") (pin "10") (pinfunction "I1_10") (pintype "input"))
      (node (ref "E31") (pin "8") (pinfunction "O_8") (pintype "output"))
    )
    (net (code "129") (name "Net-(E22C-O)") (class "Default")
      (node (ref "E22") (pin "8") (pinfunction "O_8") (pintype "output"))
      (node (ref "E26") (pin "9") (pinfunction "I_9") (pintype "input"))
    )
    (net (code "130") (name "Net-(E24A-I5)") (class "Default")
      (node (ref "E24") (pin "11") (pinfunction "I5_11") (pintype "input"))
      (node (ref "W2W1") (pin "2") (pinfunction "2_2") (pintype "passive"))
    )
    (net (code "131") (name "Net-(E24A-I6)") (class "Default")
      (node (ref "E24") (pin "12") (pinfunction "I6_12") (pintype "input"))
      (node (ref "W4W3") (pin "2") (pinfunction "2_2") (pintype "passive"))
    )
    (net (code "132") (name "Net-(E24A-O)") (class "Default")
      (node (ref "E24") (pin "3") (pinfunction "O_3") (pintype "output"))
      (node (ref "E26") (pin "11") (pinfunction "I_11") (pintype "input"))
      (node (ref "E33") (pin "5") (pinfunction "I0_5") (pintype "input"))
      (node (ref "E33") (pin "6") (pinfunction "I1_6") (pintype "input"))
    )
    (net (code "133") (name "Net-(E26B-I)") (class "Default")
      (node (ref "E26") (pin "3") (pinfunction "I_3") (pintype "input"))
      (node (ref "E43") (pin "10") (pinfunction "O_10") (pintype "open_collector"))
      (node (ref "E43") (pin "11") (pinfunction "I0_11") (pintype "input"))
      (node (ref "R14") (pin "2") (pinfunction "2_2") (pintype "passive"))
    )
    (net (code "134") (name "Net-(E26B-O)") (class "Default")
      (node (ref "E26") (pin "4") (pinfunction "O_4") (pintype "output"))
      (node (ref "E46") (pin "11") (pinfunction "I0_11") (pintype "input"))
    )
    (net (code "135") (name "Net-(E27B-O)") (class "Default")
      (node (ref "E27") (pin "6") (pinfunction "O_6") (pintype "output"))
      (node (ref "E37") (pin "2") (pinfunction "I0_2") (pintype "input"))
      (node (ref "E38") (pin "1") (pinfunction "I0_1") (pintype "input"))
    )
    (net (code "136") (name "Net-(E28D-I0)") (class "Default")
      (node (ref "E28") (pin "11") (pinfunction "I0_11") (pintype "input"))
      (node (ref "E33") (pin "3") (pinfunction "I1_3") (pintype "input"))
      (node (ref "E44") (pin "14") (pinfunction "O_14") (pintype "output"))
      (node (ref "E45") (pin "14") (pinfunction "B_14") (pintype "input"))
    )
    (net (code "137") (name "Net-(E28D-O)") (class "Default")
      (node (ref "E28") (pin "13") (pinfunction "O_13") (pintype "output"))
      (node (ref "E33") (pin "12") (pinfunction "I1_12") (pintype "input"))
    )
    (net (code "138") (name "Net-(E30A-CLR)") (class "Default")
      (node (ref "E30") (pin "1") (pinfunction "CLR_1") (pintype "input"))
      (node (ref "E37") (pin "10") (pinfunction "O_10") (pintype "output"))
    )
    (net (code "139") (name "Net-(E30A-PRE)") (class "Default")
      (node (ref "E30") (pin "10") (pinfunction "PRE_10") (pintype "input"))
      (node (ref "E30") (pin "4") (pinfunction "PRE_4") (pintype "input"))
      (node (ref "E34") (pin "10") (pinfunction "PRE_10") (pintype "input"))
      (node (ref "E34") (pin "4") (pinfunction "PRE_4") (pintype "input"))
      (node (ref "R12") (pin "1") (pinfunction "1_1") (pintype "passive"))
    )
    (net (code "140") (name "Net-(E31E-I)") (class "Default")
      (node (ref "E31") (pin "11") (pinfunction "I_11") (pintype "input"))
      (node (ref "E37") (pin "1") (pinfunction "O_1") (pintype "output"))
    )
    (net (code "141") (name "Net-(E31E-O)") (class "Default")
      (node (ref "E31") (pin "10") (pinfunction "O_10") (pintype "output"))
      (node (ref "E35") (pin "11") (pinfunction "I2_11") (pintype "input"))
      (node (ref "E35") (pin "13") (pinfunction "I2_13") (pintype "input"))
    )
    (net (code "142") (name "Net-(E32A-O)") (class "Default")
      (node (ref "E32") (pin "2") (pinfunction "O_2") (pintype "output"))
      (node (ref "E41") (pin "11") (pinfunction "I0_11") (pintype "input"))
    )
    (net (code "143") (name "Net-(E32B-O)") (class "Default")
      (node (ref "E32") (pin "4") (pinfunction "O_4") (pintype "output"))
      (node (ref "E41") (pin "9") (pinfunction "I1_9") (pintype "input"))
    )
    (net (code "144") (name "Net-(E32C-O)") (class "Default")
      (node (ref "E32") (pin "6") (pinfunction "O_6") (pintype "output"))
      (node (ref "E41") (pin "3") (pinfunction "I1_3") (pintype "input"))
    )
    (net (code "145") (name "Net-(E32D-I)") (class "Default")
      (node (ref "E32") (pin "9") (pinfunction "I_9") (pintype "input"))
      (node (ref "Q1") (pin "3") (pinfunction "C_3") (pintype "passive"))
      (node (ref "R27") (pin "1") (pinfunction "1_1") (pintype "passive"))
    )
    (net (code "146") (name "Net-(E33A-I0)") (class "Default")
      (node (ref "E33") (pin "11") (pinfunction "I0_11") (pintype "input"))
      (node (ref "E33") (pin "2") (pinfunction "I0_2") (pintype "input"))
      (node (ref "E44") (pin "2") (pinfunction "O_2") (pintype "output"))
      (node (ref "E45") (pin "1") (pinfunction "C_1") (pintype "input"))
    )
    (net (code "147") (name "Net-(E35A-O)") (class "Default")
      (node (ref "E35") (pin "12") (pinfunction "O_12") (pintype "output"))
      (node (ref "E35") (pin "3") (pinfunction "I0_3") (pintype "input"))
    )
    (net (code "148") (name "Net-(E35B-I1)") (class "Default")
      (node (ref "E35") (pin "4") (pinfunction "I1_4") (pintype "input"))
      (node (ref "E35") (pin "8") (pinfunction "O_8") (pintype "output"))
    )
    (net (code "149") (name "Net-(E36A-QA)") (class "Default")
      (node (ref "E36") (pin "12") (pinfunction "QA_12") (pintype "output"))
      (node (ref "E41") (pin "8") (pinfunction "I0_8") (pintype "input"))
    )
    (net (code "150") (name "Net-(E36A-R0(1))") (class "Default")
      (node (ref "E36") (pin "2") (pinfunction "R0(1)_2") (pintype "input"))
      (node (ref "E36") (pin "3") (pinfunction "R0(2)_3") (pintype "input"))
      (node (ref "E38") (pin "6") (pinfunction "O_6") (pintype "output"))
    )
    (net (code "151") (name "Net-(E38A-O)") (class "Default")
      (node (ref "E38") (pin "3") (pinfunction "O_3") (pintype "output"))
      (node (ref "E38") (pin "4") (pinfunction "I0_4") (pintype "input"))
    )
    (net (code "152") (name "Net-(E38C-I1)") (class "Default")
      (node (ref "E38") (pin "10") (pinfunction "I1_10") (pintype "input"))
      (node (ref "E38") (pin "11") (pinfunction "O_11") (pintype "output"))
    )
    (net (code "153") (name "Net-(E42A-O)") (class "Default")
      (node (ref "E42") (pin "3") (pinfunction "O_3") (pintype "open_collector"))
      (node (ref "E43") (pin "5") (pinfunction "I0_5") (pintype "input"))
      (node (ref "R20") (pin "1") (pinfunction "1_1") (pintype "passive"))
    )
    (net (code "154") (name "Net-(E42B-O)") (class "Default")
      (node (ref "E42") (pin "4") (pinfunction "O_4") (pintype "open_collector"))
      (node (ref "E43") (pin "3") (pinfunction "I1_3") (pintype "input"))
      (node (ref "R19") (pin "1") (pinfunction "1_1") (pintype "passive"))
    )
    (net (code "155") (name "Net-(E43C-I1)") (class "Default")
      (node (ref "E43") (pin "13") (pinfunction "O_13") (pintype "open_collector"))
      (node (ref "E43") (pin "9") (pinfunction "I1_9") (pintype "input"))
      (node (ref "R13") (pin "2") (pinfunction "2_2") (pintype "passive"))
    )
    (net (code "156") (name "Net-(E44D-O)") (class "Default")
      (node (ref "E44") (pin "13") (pinfunction "O_13") (pintype "output"))
      (node (ref "E45") (pin "15") (pinfunction "A_15") (pintype "input"))
    )
    (net (code "157") (name "Net-(Q1-B)") (class "Default")
      (node (ref "D1") (pin "C") (pinfunction "C_C") (pintype "passive"))
      (node (ref "Q1") (pin "2") (pinfunction "B_2") (pintype "passive"))
      (node (ref "R48") (pin "2") (pinfunction "2_2") (pintype "passive"))
    )
    (net (code "158") (name "Net-(Q1-E)") (class "Default")
      (node (ref "D5") (pin "C") (pinfunction "C_C") (pintype "passive"))
      (node (ref "Q1") (pin "1") (pinfunction "E_1") (pintype "passive"))
      (node (ref "R41") (pin "2") (pinfunction "2_2") (pintype "passive"))
    )
    (net (code "159") (name "Net-(Q2-E)") (class "Default")
      (node (ref "D8") (pin "A") (pinfunction "A_A") (pintype "passive"))
      (node (ref "Q2") (pin "1") (pinfunction "E_1") (pintype "passive"))
    )
    (net (code "160") (name "Net-(Q3-E)") (class "Default")
      (node (ref "D9") (pin "A") (pinfunction "A_A") (pintype "passive"))
      (node (ref "Q3") (pin "1") (pinfunction "E_1") (pintype "passive"))
    )
    (net (code "161") (name "Net-(Q4-E)") (class "Default")
      (node (ref "D7") (pin "A") (pinfunction "A_A") (pintype "passive"))
      (node (ref "Q4") (pin "1") (pinfunction "E_1") (pintype "passive"))
    )
    (net (code "162") (name "Net-(Q5-E)") (class "Default")
      (node (ref "D10") (pin "A") (pinfunction "A_A") (pintype "passive"))
      (node (ref "Q5") (pin "1") (pinfunction "E_1") (pintype "passive"))
    )
    (net (code "163") (name "Net-(R26-A)") (class "Default")
      (node (ref "R26") (pin "1") (pinfunction "A_1") (pintype "passive"))
      (node (ref "R43") (pin "2") (pinfunction "2_2") (pintype "passive"))
    )
    (net (code "164") (name "RD00") (class "Default")
      (node (ref "E16") (pin "4") (pinfunction "D_4") (pintype "input"))
      (node (ref "J1") (pin "D") (pinfunction "4_D") (pintype "bidirectional"))
      (node (ref "R4") (pin "1") (pinfunction "1_1") (pintype "passive"))
    )
    (net (code "165") (name "RD01") (class "Default")
      (node (ref "E11") (pin "4") (pinfunction "D_4") (pintype "input"))
      (node (ref "J1") (pin "L") (pinfunction "10_L") (pintype "bidirectional"))
      (node (ref "R5") (pin "1") (pinfunction "1_1") (pintype "passive"))
    )
    (net (code "166") (name "RD02") (class "Default")
      (node (ref "E06") (pin "4") (pinfunction "D_4") (pintype "input"))
      (node (ref "J1") (pin "V") (pinfunction "18_V") (pintype "bidirectional"))
      (node (ref "R7") (pin "1") (pinfunction "1_1") (pintype "passive"))
    )
    (net (code "167") (name "RMT") (class "Default")
      (node (ref "E21") (pin "4") (pinfunction "D_4") (pintype "input"))
      (node (ref "J1") (pin "F") (pinfunction "6_F") (pintype "bidirectional"))
      (node (ref "R1") (pin "1") (pinfunction "1_1") (pintype "passive"))
    )
    (net (code "168") (name "RUN") (class "Default")
      (node (ref "E20") (pin "9") (pinfunction "I0_9") (pintype "input"))
      (node (ref "EDGE$") (pin "BU2") (pinfunction "1_BU2") (pintype "bidirectional"))
    )
    (net (code "169") (name "SEL_ECHO") (class "Default")
      (node (ref "J1") (pin "N") (pinfunction "12_N") (pintype "bidirectional"))
      (node (ref "Q2") (pin "2") (pinfunction "B_2") (pintype "passive"))
      (node (ref "Q5") (pin "2") (pinfunction "B_2") (pintype "passive"))
      (node (ref "R30") (pin "2") (pinfunction "2_2") (pintype "passive"))
      (node (ref "R31") (pin "2") (pinfunction "2_2") (pintype "passive"))
      (node (ref "R32") (pin "2") (pinfunction "2_2") (pintype "passive"))
      (node (ref "R33") (pin "2") (pinfunction "2_2") (pintype "passive"))
      (node (ref "R34") (pin "2") (pinfunction "2_2") (pintype "passive"))
    )
    (net (code "170") (name "SR00") (class "Default")
      (node (ref "E05") (pin "10") (pinfunction "A2_10") (pintype "input"))
      (node (ref "E13") (pin "6") (pinfunction "D3_6") (pintype "input"))
      (node (ref "E16") (pin "11") (pinfunction "Q3_11") (pintype "output"))
    )
    (net (code "171") (name "SR01") (class "Default")
      (node (ref "E05") (pin "15") (pinfunction "A3_15") (pintype "input"))
      (node (ref "E11") (pin "11") (pinfunction "Q3_11") (pintype "output"))
      (node (ref "E13") (pin "7") (pinfunction "D4_7") (pintype "input"))
    )
    (net (code "172") (name "SR02") (class "Default")
      (node (ref "E05") (pin "6") (pinfunction "A1_6") (pintype "input"))
      (node (ref "E06") (pin "11") (pinfunction "Q3_11") (pintype "output"))
      (node (ref "E13") (pin "2") (pinfunction "D1_2") (pintype "input"))
    )
    (net (code "173") (name "SR03") (class "Default")
      (node (ref "E05") (pin "1") (pinfunction "A0_1") (pintype "input"))
      (node (ref "E16") (pin "9") (pinfunction "Q2_9") (pintype "output"))
    )
    (net (code "174") (name "SR04") (class "Default")
      (node (ref "E10") (pin "10") (pinfunction "A2_10") (pintype "input"))
      (node (ref "E11") (pin "9") (pinfunction "Q2_9") (pintype "output"))
    )
    (net (code "175") (name "SR05") (class "Default")
      (node (ref "E06") (pin "9") (pinfunction "Q2_9") (pintype "output"))
      (node (ref "E10") (pin "15") (pinfunction "A3_15") (pintype "input"))
    )
    (net (code "176") (name "SR06") (class "Default")
      (node (ref "E10") (pin "6") (pinfunction "A1_6") (pintype "input"))
      (node (ref "E16") (pin "7") (pinfunction "Q1_7") (pintype "output"))
    )
    (net (code "177") (name "SR07") (class "Default")
      (node (ref "E10") (pin "1") (pinfunction "A0_1") (pintype "input"))
      (node (ref "E11") (pin "7") (pinfunction "Q1_7") (pintype "output"))
    )
    (net (code "178") (name "SR08") (class "Default")
      (node (ref "E06") (pin "7") (pinfunction "Q1_7") (pintype "output"))
      (node (ref "E15") (pin "10") (pinfunction "A2_10") (pintype "input"))
    )
    (net (code "179") (name "SR09") (class "Default")
      (node (ref "E15") (pin "15") (pinfunction "A3_15") (pintype "input"))
      (node (ref "E16") (pin "5") (pinfunction "Q0_5") (pintype "output"))
    )
    (net (code "180") (name "SR10") (class "Default")
      (node (ref "E11") (pin "5") (pinfunction "Q0_5") (pintype "output"))
      (node (ref "E15") (pin "6") (pinfunction "A1_6") (pintype "input"))
    )
    (net (code "181") (name "SR11") (class "Default")
      (node (ref "E06") (pin "5") (pinfunction "Q0_5") (pintype "output"))
      (node (ref "E15") (pin "1") (pinfunction "A0_1") (pintype "input"))
    )
    (net (code "182") (name "SYNC") (class "Default")
      (node (ref "E09") (pin "9") (pinfunction "Q_9") (pintype "output"))
      (node (ref "E27") (pin "11") (pinfunction "I2_11") (pintype "input"))
      (node (ref "E42") (pin "2") (pinfunction "I1_2") (pintype "input"))
      (node (ref "E42") (pin "5") (pinfunction "I0_5") (pintype "input"))
    )
    (net (code "183") (name "S{slash}~{G}") (class "Default")
      (node (ref "E46") (pin "13") (pinfunction "O_13") (pintype "open_collector"))
      (node (ref "J1") (pin "JJ") (pinfunction "30_JJ") (pintype "bidirectional"))
    )
    (net (code "184") (name "TP3") (class "Default")
      (node (ref "E20") (pin "11") (pinfunction "I0_11") (pintype "input"))
      (node (ref "EDGE$") (pin "CH2") (pinfunction "1_CH2") (pintype "bidirectional"))
    )
    (net (code "185") (name "TP4") (class "Default")
      (node (ref "E44") (pin "5") (pinfunction "I1_5") (pintype "input"))
      (node (ref "EDGE$") (pin "CJ2") (pinfunction "1_CJ2") (pintype "bidirectional"))
    )
    (net (code "186") (name "TPG0") (class "Default")
      (node (ref "E14") (pin "9") (pinfunction "Q_9") (pintype "output"))
      (node (ref "E23") (pin "13") (pinfunction "I2_13") (pintype "input"))
    )
    (net (code "187") (name "T{slash}M_ENABLE") (class "Default")
      (node (ref "E46") (pin "4") (pinfunction "O_4") (pintype "open_collector"))
      (node (ref "J1") (pin "NN") (pinfunction "34_NN") (pintype "bidirectional"))
    )
    (net (code "188") (name "UNITH") (class "Default")
      (node (ref "E39") (pin "10") (pinfunction "O_10") (pintype "open_collector"))
      (node (ref "J1") (pin "LL") (pinfunction "32_LL") (pintype "bidirectional"))
    )
    (net (code "189") (name "VCC") (class "Default")
      (node (ref "C1") (pin "1") (pinfunction "1_1") (pintype "passive"))
      (node (ref "C10") (pin "1") (pinfunction "1_1") (pintype "passive"))
      (node (ref "C11") (pin "1") (pinfunction "1_1") (pintype "passive"))
      (node (ref "C12") (pin "1") (pinfunction "1_1") (pintype "passive"))
      (node (ref "C13") (pin "1") (pinfunction "1_1") (pintype "passive"))
      (node (ref "C14") (pin "1") (pinfunction "1_1") (pintype "passive"))
      (node (ref "C15") (pin "1") (pinfunction "1_1") (pintype "passive"))
      (node (ref "C16") (pin "1") (pinfunction "1_1") (pintype "passive"))
      (node (ref "C17") (pin "1") (pinfunction "1_1") (pintype "passive"))
      (node (ref "C18") (pin "1") (pinfunction "1_1") (pintype "passive"))
      (node (ref "C19") (pin "1") (pinfunction "1_1") (pintype "passive"))
      (node (ref "C2") (pin "1") (pinfunction "1_1") (pintype "passive"))
      (node (ref "C20") (pin "1") (pinfunction "1_1") (pintype "passive"))
      (node (ref "C21") (pin "1") (pinfunction "1_1") (pintype "passive"))
      (node (ref "C22") (pin "1") (pinfunction "1_1") (pintype "passive"))
      (node (ref "C23") (pin "1") (pinfunction "1_1") (pintype "passive"))
      (node (ref "C24") (pin "1") (pinfunction "1_1") (pintype "passive"))
      (node (ref "C25") (pin "1") (pinfunction "1_1") (pintype "passive"))
      (node (ref "C26") (pin "1") (pinfunction "1_1") (pintype "passive"))
      (node (ref "C27") (pin "1") (pinfunction "1_1") (pintype "passive"))
      (node (ref "C28") (pin "1") (pinfunction "1_1") (pintype "passive"))
      (node (ref "C29") (pin "1") (pinfunction "1_1") (pintype "passive"))
      (node (ref "C3") (pin "1") (pinfunction "1_1") (pintype "passive"))
      (node (ref "C30") (pin "1") (pinfunction "1_1") (pintype "passive"))
      (node (ref "C31") (pin "1") (pinfunction "1_1") (pintype "passive"))
      (node (ref "C32") (pin "1") (pinfunction "1_1") (pintype "passive"))
      (node (ref "C33") (pin "1") (pinfunction "1_1") (pintype "passive"))
      (node (ref "C34") (pin "+") (pinfunction "+_+") (pintype "passive"))
      (node (ref "C35") (pin "+") (pinfunction "+_+") (pintype "passive"))
      (node (ref "C4") (pin "1") (pinfunction "1_1") (pintype "passive"))
      (node (ref "C43") (pin "1") (pinfunction "1_1") (pintype "passive"))
      (node (ref "C45") (pin "1") (pinfunction "1_1") (pintype "passive"))
      (node (ref "C46") (pin "+") (pinfunction "+_+") (pintype "passive"))
      (node (ref "C5") (pin "1") (pinfunction "1_1") (pintype "passive"))
      (node (ref "C6") (pin "1") (pinfunction "1_1") (pintype "passive"))
      (node (ref "C7") (pin "1") (pinfunction "1_1") (pintype "passive"))
      (node (ref "C8") (pin "1") (pinfunction "1_1") (pintype "passive"))
      (node (ref "C9") (pin "1") (pinfunction "1_1") (pintype "passive"))
      (node (ref "E25") (pin "14") (pinfunction "14_14") (pintype "passive"))
      (node (ref "EDGE$") (pin "AA2") (pinfunction "1_AA2") (pintype "bidirectional"))
      (node (ref "EDGE$") (pin "BA2") (pinfunction "1_BA2") (pintype "bidirectional"))
      (node (ref "EDGE$") (pin "CA2") (pinfunction "1_CA2") (pintype "bidirectional"))
      (node (ref "R1") (pin "2") (pinfunction "2_2") (pintype "passive"))
      (node (ref "R10") (pin "2") (pinfunction "2_2") (pintype "passive"))
      (node (ref "R11") (pin "2") (pinfunction "2_2") (pintype "passive"))
      (node (ref "R12") (pin "2") (pinfunction "2_2") (pintype "passive"))
      (node (ref "R13") (pin "1") (pinfunction "1_1") (pintype "passive"))
      (node (ref "R14") (pin "1") (pinfunction "1_1") (pintype "passive"))
      (node (ref "R15") (pin "2") (pinfunction "2_2") (pintype "passive"))
      (node (ref "R16") (pin "2") (pinfunction "2_2") (pintype "passive"))
      (node (ref "R17") (pin "2") (pinfunction "2_2") (pintype "passive"))
      (node (ref "R18") (pin "2") (pinfunction "2_2") (pintype "passive"))
      (node (ref "R19") (pin "2") (pinfunction "2_2") (pintype "passive"))
      (node (ref "R2") (pin "2") (pinfunction "2_2") (pintype "passive"))
      (node (ref "R20") (pin "2") (pinfunction "2_2") (pintype "passive"))
      (node (ref "R21") (pin "2") (pinfunction "2_2") (pintype "passive"))
      (node (ref "R22") (pin "1") (pinfunction "1_1") (pintype "passive"))
      (node (ref "R23") (pin "2") (pinfunction "2_2") (pintype "passive"))
      (node (ref "R24") (pin "2") (pinfunction "2_2") (pintype "passive"))
      (node (ref "R26") (pin "2") (pinfunction "S_2") (pintype "passive"))
      (node (ref "R26") (pin "3") (pinfunction "E_3") (pintype "passive"))
      (node (ref "R27") (pin "2") (pinfunction "2_2") (pintype "passive"))
      (node (ref "R3") (pin "2") (pinfunction "2_2") (pintype "passive"))
      (node (ref "R4") (pin "2") (pinfunction "2_2") (pintype "passive"))
      (node (ref "R42") (pin "1") (pinfunction "1_1") (pintype "passive"))
      (node (ref "R5") (pin "2") (pinfunction "2_2") (pintype "passive"))
      (node (ref "R6") (pin "2") (pinfunction "2_2") (pintype "passive"))
      (node (ref "R7") (pin "2") (pinfunction "2_2") (pintype "passive"))
      (node (ref "R8") (pin "2") (pinfunction "2_2") (pintype "passive"))
      (node (ref "R9") (pin "2") (pinfunction "2_2") (pintype "passive"))
    )
    (net (code "190") (name "WD_ENAB") (class "Default")
      (node (ref "E46") (pin "10") (pinfunction "O_10") (pintype "open_collector"))
      (node (ref "J1") (pin "Z") (pinfunction "22_Z") (pintype "bidirectional"))
    )
    (net (code "191") (name "WPT") (class "Default")
      (node (ref "E39") (pin "6") (pinfunction "O_6") (pintype "open_collector"))
      (node (ref "J1") (pin "BB") (pinfunction "24_BB") (pintype "bidirectional"))
    )
    (net (code "192") (name "WRT_ECHO") (class "Default")
      (node (ref "C47") (pin "1") (pinfunction "1_1") (pintype "passive"))
      (node (ref "J1") (pin "T") (pinfunction "16_T") (pintype "bidirectional"))
      (node (ref "R48") (pin "1") (pinfunction "1_1") (pintype "passive"))
    )
    (net (code "193") (name "unconnected-(E04A-Q-Pad13)") (class "Default")
      (node (ref "E04") (pin "13") (pinfunction "Q_13") (pintype "output"))
    )
    (net (code "194") (name "unconnected-(E04B-~{Q}-Pad12)") (class "Default")
      (node (ref "E04") (pin "12") (pinfunction "~{Q}_12") (pintype "output"))
    )
    (net (code "195") (name "unconnected-(E06A-Q4-Pad12)") (class "Default")
      (node (ref "E06") (pin "12") (pinfunction "Q4_12") (pintype "output"))
    )
    (net (code "196") (name "unconnected-(E08A-~{Q}-Pad4)") (class "Default")
      (node (ref "E08") (pin "4") (pinfunction "~{Q}_4") (pintype "output"))
    )
    (net (code "197") (name "unconnected-(E09A-~{Q}-Pad6)") (class "Default")
      (node (ref "E09") (pin "6") (pinfunction "~{Q}_6") (pintype "output"))
    )
    (net (code "198") (name "unconnected-(E11A-Q4-Pad12)") (class "Default")
      (node (ref "E11") (pin "12") (pinfunction "Q4_12") (pintype "output"))
    )
    (net (code "199") (name "unconnected-(E13A-D2-Pad3)") (class "Default")
      (node (ref "E13") (pin "3") (pinfunction "D2_3") (pintype "input"))
    )
    (net (code "200") (name "unconnected-(E13A-Q1-Pad16)") (class "Default")
      (node (ref "E13") (pin "16") (pinfunction "Q1_16") (pintype "output"))
    )
    (net (code "201") (name "unconnected-(E13A-Q2-Pad15)") (class "Default")
      (node (ref "E13") (pin "15") (pinfunction "Q2_15") (pintype "output"))
    )
    (net (code "202") (name "unconnected-(E13A-Q3-Pad10)") (class "Default")
      (node (ref "E13") (pin "10") (pinfunction "Q3_10") (pintype "output"))
    )
    (net (code "203") (name "unconnected-(E13A-Q4-Pad9)") (class "Default")
      (node (ref "E13") (pin "9") (pinfunction "Q4_9") (pintype "output"))
    )
    (net (code "204") (name "unconnected-(E13A-~{Q2}-Pad14)") (class "Default")
      (node (ref "E13") (pin "14") (pinfunction "~{Q2}_14") (pintype "output"))
    )
    (net (code "205") (name "unconnected-(E16A-Q4-Pad12)") (class "Default")
      (node (ref "E16") (pin "12") (pinfunction "Q4_12") (pintype "output"))
    )
    (net (code "206") (name "unconnected-(E21A-Q4-Pad12)") (class "Default")
      (node (ref "E21") (pin "12") (pinfunction "Q4_12") (pintype "output"))
    )
    (net (code "207") (name "unconnected-(E25-Pad1)") (class "Default")
      (node (ref "E25") (pin "1") (pinfunction "1_1") (pintype "passive"))
    )
    (net (code "208") (name "unconnected-(E25-Pad2)") (class "Default")
      (node (ref "E25") (pin "2") (pinfunction "2_2") (pintype "passive"))
    )
    (net (code "209") (name "unconnected-(E25-Pad3)") (class "Default")
      (node (ref "E25") (pin "3") (pinfunction "3_3") (pintype "passive"))
    )
    (net (code "210") (name "unconnected-(E25-Pad4)") (class "Default")
      (node (ref "E25") (pin "4") (pinfunction "4_4") (pintype "passive"))
    )
    (net (code "211") (name "unconnected-(E25-Pad5)") (class "Default")
      (node (ref "E25") (pin "5") (pinfunction "5_5") (pintype "passive"))
    )
    (net (code "212") (name "unconnected-(E25-Pad6)") (class "Default")
      (node (ref "E25") (pin "6") (pinfunction "6_6") (pintype "passive"))
    )
    (net (code "213") (name "unconnected-(E25-Pad8)") (class "Default")
      (node (ref "E25") (pin "8") (pinfunction "8_8") (pintype "passive"))
    )
    (net (code "214") (name "unconnected-(E25-Pad9)") (class "Default")
      (node (ref "E25") (pin "9") (pinfunction "9_9") (pintype "passive"))
    )
    (net (code "215") (name "unconnected-(E25-Pad10)") (class "Default")
      (node (ref "E25") (pin "10") (pinfunction "10_10") (pintype "passive"))
    )
    (net (code "216") (name "unconnected-(E25-Pad11)") (class "Default")
      (node (ref "E25") (pin "11") (pinfunction "11_11") (pintype "passive"))
    )
    (net (code "217") (name "unconnected-(E25-Pad12)") (class "Default")
      (node (ref "E25") (pin "12") (pinfunction "12_12") (pintype "passive"))
    )
    (net (code "218") (name "unconnected-(E25-Pad13)") (class "Default")
      (node (ref "E25") (pin "13") (pinfunction "13_13") (pintype "passive"))
    )
    (net (code "219") (name "unconnected-(E29A-Q2-Pad9)") (class "Default")
      (node (ref "E29") (pin "9") (pinfunction "Q2_9") (pintype "output"))
    )
    (net (code "220") (name "unconnected-(E29A-Q3-Pad11)") (class "Default")
      (node (ref "E29") (pin "11") (pinfunction "Q3_11") (pintype "output"))
    )
    (net (code "221") (name "unconnected-(E29A-Q4-Pad12)") (class "Default")
      (node (ref "E29") (pin "12") (pinfunction "Q4_12") (pintype "output"))
    )
    (net (code "222") (name "unconnected-(E36A-QB-Pad9)") (class "Default")
      (node (ref "E36") (pin "9") (pinfunction "QB_9") (pintype "output"))
    )
    (net (code "223") (name "unconnected-(E36A-QC-Pad8)") (class "Default")
      (node (ref "E36") (pin "8") (pinfunction "QC_8") (pintype "output"))
    )
    (net (code "224") (name "unconnected-(E40A-I3-Pad4)") (class "Default")
      (node (ref "E40") (pin "4") (pinfunction "I3_4") (pintype "input"))
    )
    (net (code "225") (name "unconnected-(E40A-I5-Pad6)") (class "Default")
      (node (ref "E40") (pin "6") (pinfunction "I5_6") (pintype "input"))
    )
    (net (code "226") (name "unconnected-(E45A-0-Pad13)") (class "Default")
      (node (ref "E45") (pin "13") (pinfunction "0_13") (pintype "output"))
    )
    (net (code "227") (name "unconnected-(E45A-8-Pad6)") (class "Default")
      (node (ref "E45") (pin "6") (pinfunction "8_6") (pintype "output"))
    )
    (net (code "228") (name "unconnected-(E45A-9-Pad7)") (class "Default")
      (node (ref "E45") (pin "7") (pinfunction "9_7") (pintype "output"))
    )
    (net (code "229") (name "unconnected-(J1-14-PadR)") (class "Default")
      (node (ref "J1") (pin "R") (pinfunction "14_R") (pintype "bidirectional"))
    )
    (net (code "230") (name "~{CC_67X}") (class "Default")
      (node (ref "E07") (pin "11") (pinfunction "I0_11") (pintype "input"))
      (node (ref "E07") (pin "5") (pinfunction "I1_5") (pintype "input"))
      (node (ref "E07") (pin "6") (pinfunction "I0_6") (pintype "input"))
      (node (ref "E07") (pin "9") (pinfunction "I0_9") (pintype "input"))
      (node (ref "E12") (pin "10") (pinfunction "I1_10") (pintype "input"))
      (node (ref "E12") (pin "11") (pinfunction "I0_11") (pintype "input"))
      (node (ref "E12") (pin "4") (pinfunction "I0_4") (pintype "input"))
      (node (ref "E12") (pin "6") (pinfunction "I0_6") (pintype "input"))
      (node (ref "E17") (pin "11") (pinfunction "I0_11") (pintype "input"))
      (node (ref "E17") (pin "4") (pinfunction "I0_4") (pintype "input"))
      (node (ref "E17") (pin "6") (pinfunction "I0_6") (pintype "input"))
      (node (ref "E17") (pin "9") (pinfunction "I0_9") (pintype "input"))
      (node (ref "E26") (pin "10") (pinfunction "O_10") (pintype "output"))
      (node (ref "E44") (pin "10") (pinfunction "I1_10") (pintype "input"))
      (node (ref "E44") (pin "12") (pinfunction "I1_12") (pintype "input"))
      (node (ref "E44") (pin "6") (pinfunction "I0_6") (pintype "input"))
      (node (ref "E45") (pin "2") (pinfunction "D_2") (pintype "input"))
      (node (ref "R6") (pin "1") (pinfunction "1_1") (pintype "passive"))
    )
    (net (code "231") (name "~{CC_CLK_TE}") (class "Default")
      (node (ref "E26") (pin "6") (pinfunction "O_6") (pintype "output"))
      (node (ref "E27") (pin "2") (pinfunction "I1_2") (pintype "input"))
    )
    (net (code "232") (name "~{CC_DTP0}") (class "Default")
      (node (ref "E22") (pin "2") (pinfunction "I1_2") (pintype "input"))
      (node (ref "E31") (pin "13") (pinfunction "I_13") (pintype "input"))
      (node (ref "E31") (pin "4") (pinfunction "O_4") (pintype "output"))
      (node (ref "E38") (pin "13") (pinfunction "I1_13") (pintype "input"))
    )
    (net (code "233") (name "~{CC_DTP1}") (class "Default")
      (node (ref "E22") (pin "12") (pinfunction "I0_12") (pintype "input"))
      (node (ref "E22") (pin "5") (pinfunction "I1_5") (pintype "input"))
      (node (ref "E22") (pin "9") (pinfunction "I0_9") (pintype "input"))
      (node (ref "E31") (pin "2") (pinfunction "O_2") (pintype "output"))
    )
    (net (code "234") (name "~{CC_INIT}") (class "Default")
      (node (ref "E27") (pin "1") (pinfunction "I0_1") (pintype "input"))
      (node (ref "E32") (pin "10") (pinfunction "O_10") (pintype "output"))
      (node (ref "E34") (pin "1") (pinfunction "CLR_1") (pintype "input"))
      (node (ref "E34") (pin "13") (pinfunction "CLR_13") (pintype "input"))
      (node (ref "E40") (pin "12") (pinfunction "I7_12") (pintype "input"))
    )
    (net (code "235") (name "~{CC_RUN}") (class "Default")
      (node (ref "E20") (pin "14") (pinfunction "O_14") (pintype "output"))
      (node (ref "E26") (pin "13") (pinfunction "I_13") (pintype "input"))
      (node (ref "E40") (pin "3") (pinfunction "I2_3") (pintype "input"))
    )
    (net (code "236") (name "~{CC_SDLC}") (class "Default")
      (node (ref "E19") (pin "13") (pinfunction "I1_13") (pintype "input"))
      (node (ref "E37") (pin "12") (pinfunction "I1_12") (pintype "input"))
      (node (ref "E45") (pin "9") (pinfunction "4_9") (pintype "output"))
    )
    (net (code "237") (name "~{CC_SDLD}") (class "Default")
      (node (ref "E02") (pin "3") (pinfunction "I1_3") (pintype "input"))
      (node (ref "E06") (pin "13") (pinfunction "S_13") (pintype "input"))
      (node (ref "E11") (pin "13") (pinfunction "S_13") (pintype "input"))
      (node (ref "E16") (pin "13") (pinfunction "S_13") (pintype "input"))
      (node (ref "E27") (pin "5") (pinfunction "I2_5") (pintype "input"))
      (node (ref "E45") (pin "3") (pinfunction "5_3") (pintype "output"))
    )
    (net (code "238") (name "~{CC_SDRC}") (class "Default")
      (node (ref "E05") (pin "9") (pinfunction "S0_9") (pintype "input"))
      (node (ref "E10") (pin "9") (pinfunction "S0_9") (pintype "input"))
      (node (ref "E15") (pin "9") (pinfunction "S0_9") (pintype "input"))
      (node (ref "E27") (pin "3") (pinfunction "I0_3") (pintype "input"))
      (node (ref "E45") (pin "4") (pinfunction "6_4") (pintype "output"))
    )
    (net (code "239") (name "~{CC_SDRD}") (class "Default")
      (node (ref "E05") (pin "7") (pinfunction "S1_7") (pintype "input"))
      (node (ref "E10") (pin "7") (pinfunction "S1_7") (pintype "input"))
      (node (ref "E15") (pin "7") (pinfunction "S1_7") (pintype "input"))
      (node (ref "E27") (pin "4") (pinfunction "I1_4") (pintype "input"))
      (node (ref "E45") (pin "5") (pinfunction "7_5") (pintype "output"))
    )
    (net (code "240") (name "~{CC_SDSQ}") (class "Default")
      (node (ref "E32") (pin "1") (pinfunction "I_1") (pintype "input"))
      (node (ref "E45") (pin "10") (pinfunction "3_10") (pintype "output"))
    )
    (net (code "241") (name "~{CC_SDSS}") (class "Default")
      (node (ref "E32") (pin "3") (pinfunction "I_3") (pintype "input"))
      (node (ref "E45") (pin "12") (pinfunction "1_12") (pintype "output"))
    )
    (net (code "242") (name "~{CC_SDST}") (class "Default")
      (node (ref "E32") (pin "5") (pinfunction "I_5") (pintype "input"))
      (node (ref "E45") (pin "11") (pinfunction "2_11") (pintype "output"))
    )
    (net (code "243") (name "~{CC_SETDLY}") (class "Default")
      (node (ref "E03") (pin "5") (pinfunction "Q_5") (pintype "output"))
      (node (ref "E22") (pin "4") (pinfunction "I0_4") (pintype "input"))
    )
    (net (code "244") (name "~{CC_TP3}") (class "Default")
      (node (ref "E01") (pin "1") (pinfunction "I_1") (pintype "input"))
      (node (ref "E02") (pin "2") (pinfunction "I0_2") (pintype "input"))
      (node (ref "E20") (pin "13") (pinfunction "O_13") (pintype "output"))
      (node (ref "E37") (pin "11") (pinfunction "I0_11") (pintype "input"))
    )
    (net (code "245") (name "~{CC_TPG1}") (class "Default")
      (node (ref "E14") (pin "6") (pinfunction "~{Q}_6") (pintype "output"))
      (node (ref "E42") (pin "1") (pinfunction "I0_1") (pintype "input"))
    )
    (net (code "246") (name "~{CC_TPG_CLK}") (class "Default")
      (node (ref "C40") (pin "1") (pinfunction "1_1") (pintype "passive"))
      (node (ref "E04") (pin "10") (pinfunction "B_10") (pintype "input"))
      (node (ref "R25") (pin "1") (pinfunction "1_1") (pintype "passive"))
    )
    (net (code "247") (name "~{CC_UNIT}") (class "Default")
      (node (ref "E05") (pin "11") (pinfunction "B2_11") (pintype "input"))
      (node (ref "E34") (pin "8") (pinfunction "~{Q}_8") (pintype "output"))
    )
    (net (code "248") (name "~{CC_UTS}") (class "Default")
      (node (ref "E02") (pin "11") (pinfunction "I0_11") (pintype "input"))
      (node (ref "E03") (pin "8") (pinfunction "~{Q}_8") (pintype "output"))
    )
    (net (code "249") (name "~{DF_HLD}") (class "Default")
      (node (ref "E10") (pin "11") (pinfunction "B2_11") (pintype "input"))
      (node (ref "E32") (pin "8") (pinfunction "O_8") (pintype "output"))
      (node (ref "E40") (pin "2") (pinfunction "I1_2") (pintype "input"))
    )
    (net (code "250") (name "~{DF_SEL_ER}") (class "Default")
      (node (ref "E32") (pin "13") (pinfunction "I_13") (pintype "input"))
      (node (ref "E40") (pin "5") (pinfunction "I4_5") (pintype "input"))
      (node (ref "Q2") (pin "3") (pinfunction "C_3") (pintype "passive"))
      (node (ref "Q3") (pin "3") (pinfunction "C_3") (pintype "passive"))
      (node (ref "R11") (pin "1") (pinfunction "1_1") (pintype "passive"))
    )
    (net (code "251") (name "~{DF_TIME_ER}") (class "Default")
      (node (ref "E27") (pin "12") (pinfunction "O_12") (pintype "output"))
      (node (ref "E35") (pin "5") (pinfunction "I2_5") (pintype "input"))
      (node (ref "E40") (pin "1") (pinfunction "I0_1") (pintype "input"))
    )
    (net (code "252") (name "~{MTR0}") (class "Default")
      (node (ref "E10") (pin "5") (pinfunction "B1_5") (pintype "input"))
      (node (ref "E29") (pin "7") (pinfunction "Q1_7") (pintype "output"))
    )
    (net (code "253") (name "~{MTR1}") (class "Default")
      (node (ref "E10") (pin "2") (pinfunction "B0_2") (pintype "input"))
      (node (ref "E29") (pin "5") (pinfunction "Q0_5") (pintype "output"))
    )
    (net (code "254") (name "~{MTR2}") (class "Default")
      (node (ref "E15") (pin "11") (pinfunction "B2_11") (pintype "input"))
      (node (ref "E21") (pin "11") (pinfunction "Q3_11") (pintype "output"))
      (node (ref "E29") (pin "4") (pinfunction "D_4") (pintype "input"))
    )
    (net (code "255") (name "~{MTR3}") (class "Default")
      (node (ref "E15") (pin "14") (pinfunction "B3_14") (pintype "input"))
      (node (ref "E21") (pin "9") (pinfunction "Q2_9") (pintype "output"))
    )
    (net (code "256") (name "~{MTR4}") (class "Default")
      (node (ref "E15") (pin "5") (pinfunction "B1_5") (pintype "input"))
      (node (ref "E21") (pin "7") (pinfunction "Q1_7") (pintype "output"))
    )
    (net (code "257") (name "~{MTR5}") (class "Default")
      (node (ref "E15") (pin "2") (pinfunction "B0_2") (pintype "input"))
      (node (ref "E21") (pin "5") (pinfunction "Q0_5") (pintype "output"))
    )
    (net (code "258") (name "~{POWER_OK}") (class "Default")
      (node (ref "E28") (pin "6") (pinfunction "I0_6") (pintype "input"))
      (node (ref "EDGE$") (pin "BV2") (pinfunction "1_BV2") (pintype "bidirectional"))
    )
    (net (code "259") (name "~{RTT}") (class "Default")
      (node (ref "E42") (pin "6") (pinfunction "I1_6") (pintype "input"))
      (node (ref "J1") (pin "J") (pinfunction "8_J") (pintype "bidirectional"))
      (node (ref "R18") (pin "1") (pinfunction "1_1") (pintype "passive"))
    )
    (net (code "260") (name "~{SKIP}") (class "Default")
      (node (ref "E41") (pin "1") (pinfunction "O_1") (pintype "open_collector"))
      (node (ref "E41") (pin "10") (pinfunction "O_10") (pintype "open_collector"))
      (node (ref "E41") (pin "13") (pinfunction "O_13") (pintype "open_collector"))
      (node (ref "EDGE$") (pin "CS1") (pinfunction "1_CS1") (pintype "bidirectional"))
    )
  )
)
